# MCU.net
KiCad netlist of a schematic drawn in Altium Designer
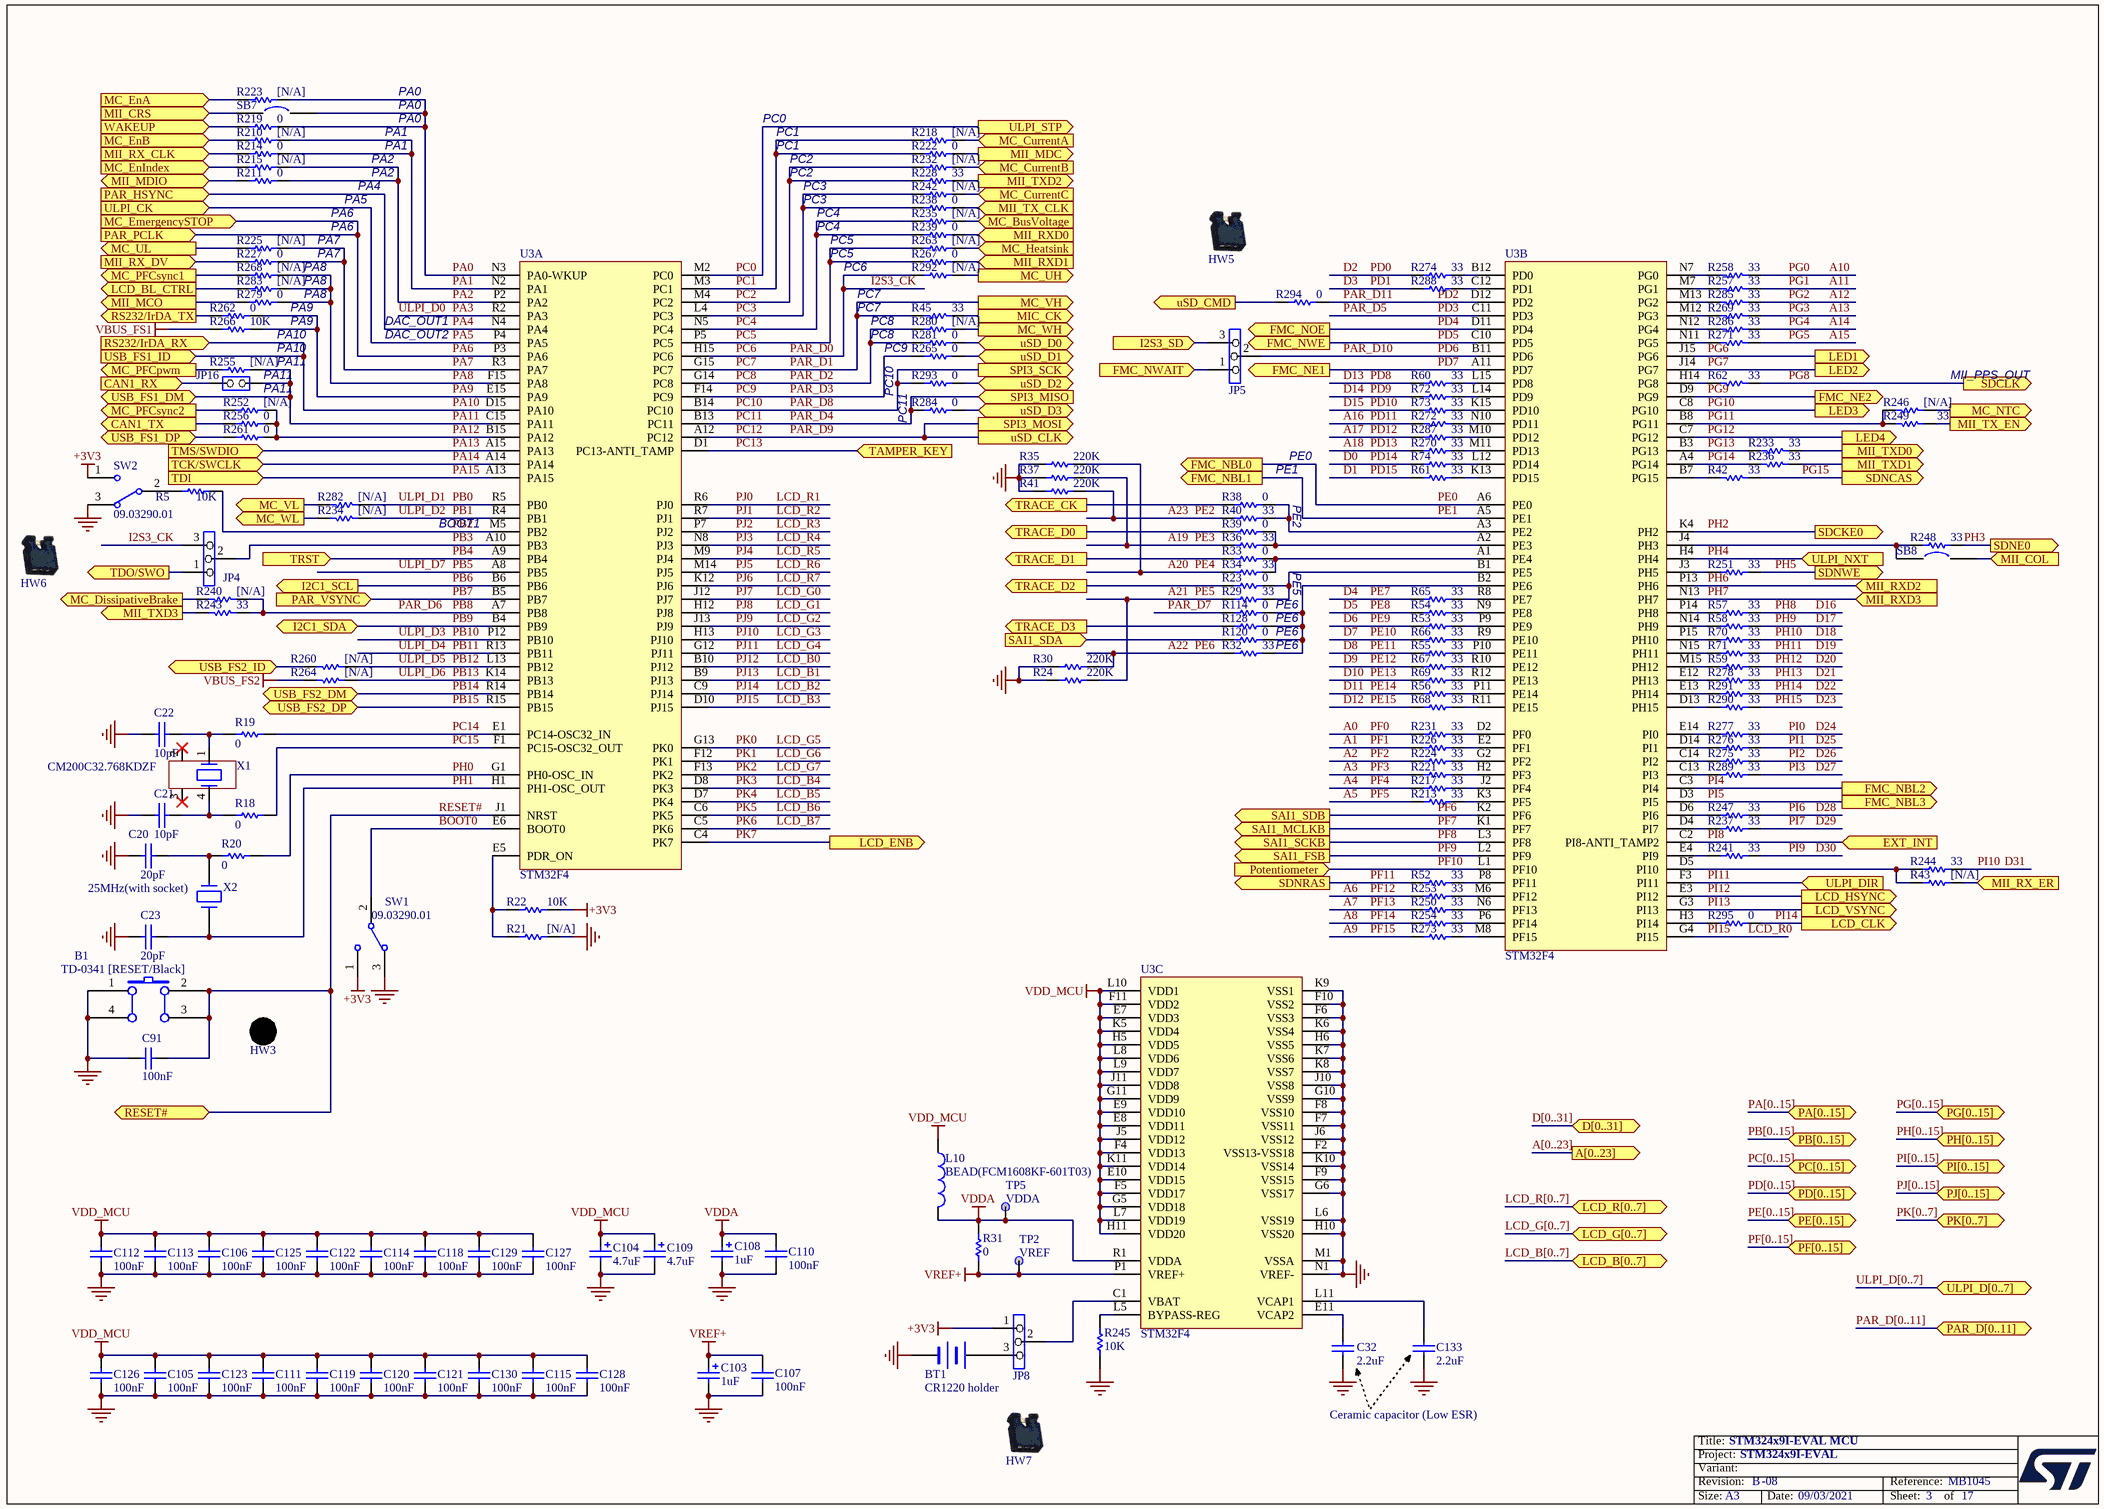
[diagram p0: MCU.SchDoc]

(export (version "E")
  (design (tool "Eeschema 10.0.6"))
  (components
    (comp (ref "B1")
      (value "TD-0341 [RESET/Black]")
      (footprint "PB10")
      (description "SE PUSHBUTTON")
      (libsource (lib "Documents") (part "SW PUSHBUTTON"))
    )
    (comp (ref "BT1")
      (value "CR1220 holder")
      (footprint "BAT_2SM_CR1220")
      (description "Battery")
      (libsource (lib "*") (part "BATTERY"))
    )
    (comp (ref "C20")
      (value "20pF")
      (footprint "0603C")
      (description "Capacitor")
      (libsource (lib "*") (part "CAP"))
    )
    (comp (ref "C21")
      (value "10pF")
      (footprint "0603C")
      (description "Capacitor")
      (libsource (lib "") (part "CAP_1"))
    )
    (comp (ref "C22")
      (value "10pF")
      (footprint "0603C")
      (description "Capacitor")
      (libsource (lib "") (part "CAP_1"))
    )
    (comp (ref "C23")
      (value "20pF")
      (footprint "0603C")
      (description "Capacitor")
      (libsource (lib "*") (part "CAP"))
    )
    (comp (ref "C32")
      (value "2.2uF")
      (footprint "1206C")
      (description "Capacitor")
      (fields (field (name "PUBLISHER") "Altium Limited"))
      (libsource (lib "Miscellaneous Devices") (part "Cap"))
    )
    (comp (ref "C91")
      (value "100nF")
      (footprint "0603C")
      (description "Capacitor")
      (fields (field (name "PUBLISHER") "Altium Limited"))
      (libsource (lib "Miscellaneous Devices") (part "CAP"))
    )
    (comp (ref "C103")
      (value "1uF")
      (footprint "TAN-A")
      (description "Polarized Capacitor (Radial)")
      (fields (field (name "PUBLISHER") "Altium Limited"))
      (libsource (lib "Miscellaneous Devices") (part "Cap Pol1"))
    )
    (comp (ref "C104")
      (value "4.7uF")
      (footprint "TAN-A")
      (description "Polarized Capacitor (Radial)")
      (fields (field (name "PUBLISHER") "Altium Limited"))
      (libsource (lib "Miscellaneous Devices") (part "Cap Pol1"))
    )
    (comp (ref "C105")
      (value "100nF")
      (footprint "0402C")
      (description "Capacitor")
      (fields (field (name "PUBLISHER") "Altium Limited"))
      (libsource (lib "Miscellaneous Devices") (part "CAP"))
    )
    (comp (ref "C106")
      (value "100nF")
      (footprint "0402C")
      (description "Capacitor")
      (fields (field (name "PUBLISHER") "Altium Limited"))
      (libsource (lib "Miscellaneous Devices") (part "CAP"))
    )
    (comp (ref "C107")
      (value "100nF")
      (footprint "0402C")
      (description "Capacitor")
      (fields (field (name "PUBLISHER") "Altium Limited"))
      (libsource (lib "Miscellaneous Devices") (part "Cap"))
    )
    (comp (ref "C108")
      (value "1uF")
      (footprint "TAN-A")
      (description "Polarized Capacitor (Radial)")
      (fields (field (name "PUBLISHER") "Altium Limited"))
      (libsource (lib "Miscellaneous Devices") (part "Cap Pol1"))
    )
    (comp (ref "C109")
      (value "4.7uF")
      (footprint "TAN-A")
      (description "Polarized Capacitor (Radial)")
      (fields (field (name "PUBLISHER") "Altium Limited"))
      (libsource (lib "Miscellaneous Devices") (part "Cap Pol1"))
    )
    (comp (ref "C110")
      (value "100nF")
      (footprint "0402C")
      (description "Capacitor")
      (fields (field (name "PUBLISHER") "Altium Limited"))
      (libsource (lib "Miscellaneous Devices") (part "Cap"))
    )
    (comp (ref "C111")
      (value "100nF")
      (footprint "0402C")
      (description "Capacitor")
      (fields (field (name "PUBLISHER") "Altium Limited"))
      (libsource (lib "Miscellaneous Devices") (part "CAP"))
    )
    (comp (ref "C112")
      (value "100nF")
      (footprint "0402C")
      (description "Capacitor")
      (fields (field (name "PUBLISHER") "Altium Limited"))
      (libsource (lib "Miscellaneous Devices") (part "CAP"))
    )
    (comp (ref "C113")
      (value "100nF")
      (footprint "0402C")
      (description "Capacitor")
      (fields (field (name "PUBLISHER") "Altium Limited"))
      (libsource (lib "Miscellaneous Devices") (part "CAP"))
    )
    (comp (ref "C114")
      (value "100nF")
      (footprint "0402C")
      (description "Capacitor")
      (fields (field (name "PUBLISHER") "Altium Limited"))
      (libsource (lib "Miscellaneous Devices") (part "CAP"))
    )
    (comp (ref "C115")
      (value "100nF")
      (footprint "0402C")
      (description "Capacitor")
      (fields (field (name "PUBLISHER") "Altium Limited"))
      (libsource (lib "Miscellaneous Devices") (part "CAP"))
    )
    (comp (ref "C118")
      (value "100nF")
      (footprint "0402C")
      (description "Capacitor")
      (fields (field (name "PUBLISHER") "Altium Limited"))
      (libsource (lib "Miscellaneous Devices") (part "CAP"))
    )
    (comp (ref "C119")
      (value "100nF")
      (footprint "0402C")
      (description "Capacitor")
      (fields (field (name "PUBLISHER") "Altium Limited"))
      (libsource (lib "Miscellaneous Devices") (part "CAP"))
    )
    (comp (ref "C120")
      (value "100nF")
      (footprint "0402C")
      (description "Capacitor")
      (fields (field (name "PUBLISHER") "Altium Limited"))
      (libsource (lib "Miscellaneous Devices") (part "CAP"))
    )
    (comp (ref "C121")
      (value "100nF")
      (footprint "0402C")
      (description "Capacitor")
      (fields (field (name "PUBLISHER") "Altium Limited"))
      (libsource (lib "Miscellaneous Devices") (part "CAP"))
    )
    (comp (ref "C122")
      (value "100nF")
      (footprint "0402C")
      (description "Capacitor")
      (fields (field (name "PUBLISHER") "Altium Limited"))
      (libsource (lib "Miscellaneous Devices") (part "CAP"))
    )
    (comp (ref "C123")
      (value "100nF")
      (footprint "0402C")
      (description "Capacitor")
      (fields (field (name "PUBLISHER") "Altium Limited"))
      (libsource (lib "Miscellaneous Devices") (part "CAP"))
    )
    (comp (ref "C125")
      (value "100nF")
      (footprint "0402C")
      (description "Capacitor")
      (fields (field (name "PUBLISHER") "Altium Limited"))
      (libsource (lib "Miscellaneous Devices") (part "CAP"))
    )
    (comp (ref "C126")
      (value "100nF")
      (footprint "0402C")
      (description "Capacitor")
      (fields (field (name "PUBLISHER") "Altium Limited"))
      (libsource (lib "Miscellaneous Devices") (part "CAP"))
    )
    (comp (ref "C127")
      (value "100nF")
      (footprint "0402C")
      (description "Capacitor")
      (fields (field (name "PUBLISHER") "Altium Limited"))
      (libsource (lib "Miscellaneous Devices") (part "CAP"))
    )
    (comp (ref "C128")
      (value "100nF")
      (footprint "0402C")
      (description "Capacitor")
      (fields (field (name "PUBLISHER") "Altium Limited"))
      (libsource (lib "Miscellaneous Devices") (part "CAP"))
    )
    (comp (ref "C129")
      (value "100nF")
      (footprint "0402C")
      (description "Capacitor")
      (fields (field (name "PUBLISHER") "Altium Limited"))
      (libsource (lib "Miscellaneous Devices") (part "CAP"))
    )
    (comp (ref "C130")
      (value "100nF")
      (footprint "0402C")
      (description "Capacitor")
      (fields (field (name "PUBLISHER") "Altium Limited"))
      (libsource (lib "Miscellaneous Devices") (part "CAP"))
    )
    (comp (ref "C133")
      (value "2.2uF")
      (footprint "1206C")
      (description "Capacitor")
      (fields (field (name "PUBLISHER") "Altium Limited"))
      (libsource (lib "Miscellaneous Devices") (part "Cap"))
    )
    (comp (ref "HW3") (value "BUTTON_HAT_BLACK") (libsource (lib "mb1045") (part "BUTTON_HAT_BLACK")))
    (comp (ref "HW5") (value "JUMPER_OPEN") (libsource (lib "mb1045") (part "JUMPER_OPEN")))
    (comp (ref "HW6") (value "JUMPER_OPEN") (libsource (lib "mb1045") (part "JUMPER_OPEN")))
    (comp (ref "HW7") (value "JUMPER_OPEN") (libsource (lib "mb1045") (part "JUMPER_OPEN")))
    (comp (ref "JP4") (value "~") (footprint "SIP3") (libsource (lib "STR910_SCHLIB") (part "Jumper3")))
    (comp (ref "JP5") (value "~") (footprint "SIP3") (libsource (lib "STR910_SCHLIB") (part "Jumper3")))
    (comp (ref "JP8") (value "~") (footprint "SIP3") (libsource (lib "") (part "Jumper3_1")))
    (comp (ref "JP16") (value "~") (footprint "SIP2") (libsource (lib "*") (part "JP2")))
    (comp (ref "L10")
      (value "BEAD(FCM1608KF-601T03)")
      (footprint "0603L")
      (description "Inductor")
      (fields (field (name "PUBLISHER") "Altium Limited"))
      (libsource (lib "Miscellaneous Devices") (part "Inductor"))
    )
    (comp (ref "R5")
      (value "10K")
      (footprint "0603R")
      (description "Resistor")
      (fields (field (name "PUBLISHER") "Altium Limited"))
      (libsource (lib "Miscellaneous Devices") (part "Res1"))
    )
    (comp (ref "R18")
      (value "0")
      (footprint "0603R")
      (description "Resistor")
      (fields (field (name "PUBLISHER") "Altium Limited"))
      (libsource (lib "") (part "Res1_1"))
    )
    (comp (ref "R19")
      (value "0")
      (footprint "0603R")
      (description "Resistor")
      (fields (field (name "PUBLISHER") "Altium Limited"))
      (libsource (lib "") (part "Res1_1"))
    )
    (comp (ref "R20")
      (value "0")
      (footprint "0603R")
      (description "Resistor")
      (fields (field (name "PUBLISHER") "Altium Limited"))
      (libsource (lib "Miscellaneous Devices") (part "Res1"))
    )
    (comp (ref "R21")
      (value "[N/A]")
      (footprint "0603R")
      (description "Resistor")
      (fields (field (name "PUBLISHER") "Altium Limited"))
      (libsource (lib "Miscellaneous Devices") (part "Res1"))
    )
    (comp (ref "R22")
      (value "10K")
      (footprint "0603R")
      (description "Resistor")
      (fields (field (name "PUBLISHER") "Altium Limited"))
      (libsource (lib "Miscellaneous Devices") (part "Res1"))
    )
    (comp (ref "R23")
      (value "0")
      (footprint "0603R")
      (description "Resistor")
      (fields (field (name "PUBLISHER") "Altium Limited"))
      (libsource (lib "Miscellaneous Devices") (part "Res1"))
    )
    (comp (ref "R24")
      (value "220K")
      (footprint "0603R")
      (description "Resistor")
      (fields (field (name "PUBLISHER") "Altium Limited"))
      (libsource (lib "Miscellaneous Devices") (part "res1"))
    )
    (comp (ref "R29")
      (value "33")
      (footprint "0402R")
      (description "Resistor")
      (fields (field (name "PUBLISHER") "Altium Limited"))
      (libsource (lib "Miscellaneous Devices") (part "Res1"))
    )
    (comp (ref "R30")
      (value "220K")
      (footprint "0603R")
      (description "Resistor")
      (fields (field (name "PUBLISHER") "Altium Limited"))
      (libsource (lib "Miscellaneous Devices") (part "res1"))
    )
    (comp (ref "R31")
      (value "0")
      (footprint "0603R")
      (description "Resistor")
      (fields (field (name "PUBLISHER") "Altium Limited"))
      (libsource (lib "Miscellaneous Devices") (part "Res1"))
    )
    (comp (ref "R32")
      (value "33")
      (footprint "0402R")
      (description "Resistor")
      (fields (field (name "PUBLISHER") "Altium Limited"))
      (libsource (lib "Miscellaneous Devices") (part "Res1"))
    )
    (comp (ref "R33")
      (value "0")
      (footprint "0603R")
      (description "Resistor")
      (fields (field (name "PUBLISHER") "Altium Limited"))
      (libsource (lib "Miscellaneous Devices") (part "Res1"))
    )
    (comp (ref "R34")
      (value "33")
      (footprint "0402R")
      (description "Resistor")
      (fields (field (name "PUBLISHER") "Altium Limited"))
      (libsource (lib "Miscellaneous Devices") (part "Res1"))
    )
    (comp (ref "R35")
      (value "220K")
      (footprint "0603R")
      (description "Resistor")
      (fields (field (name "PUBLISHER") "Altium Limited"))
      (libsource (lib "Miscellaneous Devices") (part "res1"))
    )
    (comp (ref "R36")
      (value "33")
      (footprint "0402R")
      (description "Resistor")
      (fields (field (name "PUBLISHER") "Altium Limited"))
      (libsource (lib "Miscellaneous Devices") (part "Res1"))
    )
    (comp (ref "R37")
      (value "220K")
      (footprint "0603R")
      (description "Resistor")
      (fields (field (name "PUBLISHER") "Altium Limited"))
      (libsource (lib "Miscellaneous Devices") (part "res1"))
    )
    (comp (ref "R38")
      (value "0")
      (footprint "0603R")
      (description "Resistor")
      (fields (field (name "PUBLISHER") "Altium Limited"))
      (libsource (lib "Miscellaneous Devices") (part "Res1"))
    )
    (comp (ref "R39")
      (value "0")
      (footprint "0603R")
      (description "Resistor")
      (fields (field (name "PUBLISHER") "Altium Limited"))
      (libsource (lib "Miscellaneous Devices") (part "Res1"))
    )
    (comp (ref "R40")
      (value "33")
      (footprint "0402R")
      (description "Resistor")
      (fields (field (name "PUBLISHER") "Altium Limited"))
      (libsource (lib "Miscellaneous Devices") (part "Res1"))
    )
    (comp (ref "R41")
      (value "220K")
      (footprint "0603R")
      (description "Resistor")
      (fields (field (name "PUBLISHER") "Altium Limited"))
      (libsource (lib "Miscellaneous Devices") (part "res1"))
    )
    (comp (ref "R42")
      (value "33")
      (footprint "0402R")
      (description "Resistor")
      (fields (field (name "PUBLISHER") "Altium Limited"))
      (libsource (lib "Miscellaneous Devices") (part "Res1"))
    )
    (comp (ref "R43")
      (value "[N/A]")
      (footprint "0603R")
      (description "Resistor")
      (fields (field (name "PUBLISHER") "Altium Limited"))
      (libsource (lib "Miscellaneous Devices") (part "Res1"))
    )
    (comp (ref "R45")
      (value "33")
      (footprint "0603R")
      (description "Resistor")
      (fields (field (name "PUBLISHER") "Altium Limited"))
      (libsource (lib "Miscellaneous Devices") (part "Res1"))
    )
    (comp (ref "R52")
      (value "33")
      (footprint "0402R")
      (description "Resistor")
      (fields (field (name "PUBLISHER") "Altium Limited"))
      (libsource (lib "Miscellaneous Devices") (part "Res1"))
    )
    (comp (ref "R53")
      (value "33")
      (footprint "0402R")
      (description "Resistor")
      (fields (field (name "PUBLISHER") "Altium Limited"))
      (libsource (lib "Miscellaneous Devices") (part "Res1"))
    )
    (comp (ref "R54")
      (value "33")
      (footprint "0402R")
      (description "Resistor")
      (fields (field (name "PUBLISHER") "Altium Limited"))
      (libsource (lib "Miscellaneous Devices") (part "Res1"))
    )
    (comp (ref "R55")
      (value "33")
      (footprint "0402R")
      (description "Resistor")
      (fields (field (name "PUBLISHER") "Altium Limited"))
      (libsource (lib "Miscellaneous Devices") (part "Res1"))
    )
    (comp (ref "R56")
      (value "33")
      (footprint "0402R")
      (description "Resistor")
      (fields (field (name "PUBLISHER") "Altium Limited"))
      (libsource (lib "Miscellaneous Devices") (part "Res1"))
    )
    (comp (ref "R57")
      (value "33")
      (footprint "0402R")
      (description "Resistor")
      (fields (field (name "PUBLISHER") "Altium Limited"))
      (libsource (lib "Miscellaneous Devices") (part "Res1"))
    )
    (comp (ref "R58")
      (value "33")
      (footprint "0402R")
      (description "Resistor")
      (fields (field (name "PUBLISHER") "Altium Limited"))
      (libsource (lib "Miscellaneous Devices") (part "Res1"))
    )
    (comp (ref "R59")
      (value "33")
      (footprint "0402R")
      (description "Resistor")
      (fields (field (name "PUBLISHER") "Altium Limited"))
      (libsource (lib "Miscellaneous Devices") (part "Res1"))
    )
    (comp (ref "R60")
      (value "33")
      (footprint "0402R")
      (description "Resistor")
      (fields (field (name "PUBLISHER") "Altium Limited"))
      (libsource (lib "Miscellaneous Devices") (part "Res1"))
    )
    (comp (ref "R61")
      (value "33")
      (footprint "0402R")
      (description "Resistor")
      (fields (field (name "PUBLISHER") "Altium Limited"))
      (libsource (lib "Miscellaneous Devices") (part "Res1"))
    )
    (comp (ref "R62")
      (value "33")
      (footprint "0402R")
      (description "Resistor")
      (fields (field (name "PUBLISHER") "Altium Limited"))
      (libsource (lib "Miscellaneous Devices") (part "Res1"))
    )
    (comp (ref "R65")
      (value "33")
      (footprint "0402R")
      (description "Resistor")
      (fields (field (name "PUBLISHER") "Altium Limited"))
      (libsource (lib "Miscellaneous Devices") (part "Res1"))
    )
    (comp (ref "R66")
      (value "33")
      (footprint "0402R")
      (description "Resistor")
      (fields (field (name "PUBLISHER") "Altium Limited"))
      (libsource (lib "Miscellaneous Devices") (part "Res1"))
    )
    (comp (ref "R67")
      (value "33")
      (footprint "0402R")
      (description "Resistor")
      (fields (field (name "PUBLISHER") "Altium Limited"))
      (libsource (lib "Miscellaneous Devices") (part "Res1"))
    )
    (comp (ref "R68")
      (value "33")
      (footprint "0402R")
      (description "Resistor")
      (fields (field (name "PUBLISHER") "Altium Limited"))
      (libsource (lib "Miscellaneous Devices") (part "Res1"))
    )
    (comp (ref "R69")
      (value "33")
      (footprint "0402R")
      (description "Resistor")
      (fields (field (name "PUBLISHER") "Altium Limited"))
      (libsource (lib "Miscellaneous Devices") (part "Res1"))
    )
    (comp (ref "R70")
      (value "33")
      (footprint "0402R")
      (description "Resistor")
      (fields (field (name "PUBLISHER") "Altium Limited"))
      (libsource (lib "Miscellaneous Devices") (part "Res1"))
    )
    (comp (ref "R71")
      (value "33")
      (footprint "0402R")
      (description "Resistor")
      (fields (field (name "PUBLISHER") "Altium Limited"))
      (libsource (lib "Miscellaneous Devices") (part "Res1"))
    )
    (comp (ref "R72")
      (value "33")
      (footprint "0402R")
      (description "Resistor")
      (fields (field (name "PUBLISHER") "Altium Limited"))
      (libsource (lib "Miscellaneous Devices") (part "Res1"))
    )
    (comp (ref "R73")
      (value "33")
      (footprint "0402R")
      (description "Resistor")
      (fields (field (name "PUBLISHER") "Altium Limited"))
      (libsource (lib "Miscellaneous Devices") (part "Res1"))
    )
    (comp (ref "R74")
      (value "33")
      (footprint "0402R")
      (description "Resistor")
      (fields (field (name "PUBLISHER") "Altium Limited"))
      (libsource (lib "Miscellaneous Devices") (part "Res1"))
    )
    (comp (ref "R114")
      (value "0")
      (footprint "0603R")
      (description "Resistor")
      (fields (field (name "PUBLISHER") "Altium Limited"))
      (libsource (lib "Miscellaneous Devices") (part "Res1"))
    )
    (comp (ref "R120")
      (value "0")
      (footprint "0603R")
      (description "Resistor")
      (fields (field (name "PUBLISHER") "Altium Limited"))
      (libsource (lib "Miscellaneous Devices") (part "Res1"))
    )
    (comp (ref "R128")
      (value "0")
      (footprint "0603R")
      (description "Resistor")
      (fields (field (name "PUBLISHER") "Altium Limited"))
      (libsource (lib "Miscellaneous Devices") (part "Res1"))
    )
    (comp (ref "R210")
      (value "[N/A]")
      (footprint "0603R")
      (description "Resistor")
      (fields (field (name "PUBLISHER") "Altium Limited"))
      (libsource (lib "Miscellaneous Devices") (part "Res1"))
    )
    (comp (ref "R211")
      (value "0")
      (footprint "0603R")
      (description "Resistor")
      (fields (field (name "PUBLISHER") "Altium Limited"))
      (libsource (lib "Miscellaneous Devices") (part "Res1"))
    )
    (comp (ref "R213")
      (value "33")
      (footprint "0402R")
      (description "Resistor")
      (fields (field (name "PUBLISHER") "Altium Limited"))
      (libsource (lib "Miscellaneous Devices") (part "Res1"))
    )
    (comp (ref "R214")
      (value "0")
      (footprint "0603R")
      (description "Resistor")
      (fields (field (name "PUBLISHER") "Altium Limited"))
      (libsource (lib "Miscellaneous Devices") (part "Res1"))
    )
    (comp (ref "R215")
      (value "[N/A]")
      (footprint "0603R")
      (description "Resistor")
      (fields (field (name "PUBLISHER") "Altium Limited"))
      (libsource (lib "Miscellaneous Devices") (part "Res1"))
    )
    (comp (ref "R217")
      (value "33")
      (footprint "0402R")
      (description "Resistor")
      (fields (field (name "PUBLISHER") "Altium Limited"))
      (libsource (lib "Miscellaneous Devices") (part "Res1"))
    )
    (comp (ref "R218")
      (value "[N/A]")
      (footprint "0603R")
      (description "Resistor")
      (fields (field (name "PUBLISHER") "Altium Limited"))
      (libsource (lib "Miscellaneous Devices") (part "Res1"))
    )
    (comp (ref "R219")
      (value "0")
      (footprint "0603R")
      (description "Resistor")
      (fields (field (name "PUBLISHER") "Altium Limited"))
      (libsource (lib "Miscellaneous Devices") (part "Res1"))
    )
    (comp (ref "R221")
      (value "33")
      (footprint "0402R")
      (description "Resistor")
      (fields (field (name "PUBLISHER") "Altium Limited"))
      (libsource (lib "Miscellaneous Devices") (part "Res1"))
    )
    (comp (ref "R222")
      (value "0")
      (footprint "0603R")
      (description "Resistor")
      (fields (field (name "PUBLISHER") "Altium Limited"))
      (libsource (lib "Miscellaneous Devices") (part "Res1"))
    )
    (comp (ref "R223")
      (value "[N/A]")
      (footprint "0603R")
      (description "Resistor")
      (fields (field (name "PUBLISHER") "Altium Limited"))
      (libsource (lib "Miscellaneous Devices") (part "Res1"))
    )
    (comp (ref "R224")
      (value "33")
      (footprint "0402R")
      (description "Resistor")
      (fields (field (name "PUBLISHER") "Altium Limited"))
      (libsource (lib "Miscellaneous Devices") (part "Res1"))
    )
    (comp (ref "R225")
      (value "[N/A]")
      (footprint "0603R")
      (description "Resistor")
      (fields (field (name "PUBLISHER") "Altium Limited"))
      (libsource (lib "Miscellaneous Devices") (part "Res1"))
    )
    (comp (ref "R226")
      (value "33")
      (footprint "0402R")
      (description "Resistor")
      (fields (field (name "PUBLISHER") "Altium Limited"))
      (libsource (lib "Miscellaneous Devices") (part "Res1"))
    )
    (comp (ref "R227")
      (value "0")
      (footprint "0603R")
      (description "Resistor")
      (fields (field (name "PUBLISHER") "Altium Limited"))
      (libsource (lib "Miscellaneous Devices") (part "Res1"))
    )
    (comp (ref "R228")
      (value "33")
      (footprint "0603R")
      (description "Resistor")
      (fields (field (name "PUBLISHER") "Altium Limited"))
      (libsource (lib "Miscellaneous Devices") (part "Res1"))
    )
    (comp (ref "R231")
      (value "33")
      (footprint "0402R")
      (description "Resistor")
      (fields (field (name "PUBLISHER") "Altium Limited"))
      (libsource (lib "Miscellaneous Devices") (part "Res1"))
    )
    (comp (ref "R232")
      (value "[N/A]")
      (footprint "0603R")
      (description "Resistor")
      (fields (field (name "PUBLISHER") "Altium Limited"))
      (libsource (lib "Miscellaneous Devices") (part "Res1"))
    )
    (comp (ref "R233")
      (value "33")
      (footprint "0603R")
      (description "Resistor")
      (fields (field (name "PUBLISHER") "Altium Limited"))
      (libsource (lib "Miscellaneous Devices") (part "Res1"))
    )
    (comp (ref "R234")
      (value "[N/A]")
      (footprint "0603R")
      (description "Resistor")
      (fields (field (name "PUBLISHER") "Altium Limited"))
      (libsource (lib "Miscellaneous Devices") (part "Res1"))
    )
    (comp (ref "R235")
      (value "[N/A]")
      (footprint "0603R")
      (description "Resistor")
      (fields (field (name "PUBLISHER") "Altium Limited"))
      (libsource (lib "Miscellaneous Devices") (part "Res1"))
    )
    (comp (ref "R236")
      (value "33")
      (footprint "0603R")
      (description "Resistor")
      (fields (field (name "PUBLISHER") "Altium Limited"))
      (libsource (lib "Miscellaneous Devices") (part "Res1"))
    )
    (comp (ref "R237")
      (value "33")
      (footprint "0402R")
      (description "Resistor")
      (fields (field (name "PUBLISHER") "Altium Limited"))
      (libsource (lib "Miscellaneous Devices") (part "Res1"))
    )
    (comp (ref "R238")
      (value "0")
      (footprint "0603R")
      (description "Resistor")
      (fields (field (name "PUBLISHER") "Altium Limited"))
      (libsource (lib "Miscellaneous Devices") (part "Res1"))
    )
    (comp (ref "R239")
      (value "0")
      (footprint "0603R")
      (description "Resistor")
      (fields (field (name "PUBLISHER") "Altium Limited"))
      (libsource (lib "Miscellaneous Devices") (part "Res1"))
    )
    (comp (ref "R240")
      (value "[N/A]")
      (footprint "0603R")
      (description "Resistor")
      (fields (field (name "PUBLISHER") "Altium Limited"))
      (libsource (lib "Miscellaneous Devices") (part "Res1"))
    )
    (comp (ref "R241")
      (value "33")
      (footprint "0402R")
      (description "Resistor")
      (fields (field (name "PUBLISHER") "Altium Limited"))
      (libsource (lib "Miscellaneous Devices") (part "Res1"))
    )
    (comp (ref "R242")
      (value "[N/A]")
      (footprint "0603R")
      (description "Resistor")
      (fields (field (name "PUBLISHER") "Altium Limited"))
      (libsource (lib "Miscellaneous Devices") (part "Res1"))
    )
    (comp (ref "R243")
      (value "33")
      (footprint "0603R")
      (description "Resistor")
      (fields (field (name "PUBLISHER") "Altium Limited"))
      (libsource (lib "Miscellaneous Devices") (part "Res1"))
    )
    (comp (ref "R244")
      (value "33")
      (footprint "0402R")
      (description "Resistor")
      (fields (field (name "PUBLISHER") "Altium Limited"))
      (libsource (lib "Miscellaneous Devices") (part "Res1"))
    )
    (comp (ref "R245")
      (value "10K")
      (footprint "0603R")
      (description "Resistor")
      (fields (field (name "PUBLISHER") "Altium Limited"))
      (libsource (lib "Miscellaneous Devices") (part "Res1"))
    )
    (comp (ref "R246")
      (value "[N/A]")
      (footprint "0603R")
      (description "Resistor")
      (fields (field (name "PUBLISHER") "Altium Limited"))
      (libsource (lib "Miscellaneous Devices") (part "Res1"))
    )
    (comp (ref "R247")
      (value "33")
      (footprint "0402R")
      (description "Resistor")
      (fields (field (name "PUBLISHER") "Altium Limited"))
      (libsource (lib "Miscellaneous Devices") (part "Res1"))
    )
    (comp (ref "R248")
      (value "33")
      (footprint "0402R")
      (description "Resistor")
      (fields (field (name "PUBLISHER") "Altium Limited"))
      (libsource (lib "Miscellaneous Devices") (part "Res1"))
    )
    (comp (ref "R249")
      (value "33")
      (footprint "0603R")
      (description "Resistor")
      (fields (field (name "PUBLISHER") "Altium Limited"))
      (libsource (lib "Miscellaneous Devices") (part "Res1"))
    )
    (comp (ref "R250")
      (value "33")
      (footprint "0402R")
      (description "Resistor")
      (fields (field (name "PUBLISHER") "Altium Limited"))
      (libsource (lib "Miscellaneous Devices") (part "Res1"))
    )
    (comp (ref "R251")
      (value "33")
      (footprint "0402R")
      (description "Resistor")
      (fields (field (name "PUBLISHER") "Altium Limited"))
      (libsource (lib "Miscellaneous Devices") (part "Res1"))
    )
    (comp (ref "R252")
      (value "[N/A]")
      (footprint "0603R")
      (description "Resistor")
      (fields (field (name "PUBLISHER") "Altium Limited"))
      (libsource (lib "Miscellaneous Devices") (part "Res1"))
    )
    (comp (ref "R253")
      (value "33")
      (footprint "0402R")
      (description "Resistor")
      (fields (field (name "PUBLISHER") "Altium Limited"))
      (libsource (lib "Miscellaneous Devices") (part "Res1"))
    )
    (comp (ref "R254")
      (value "33")
      (footprint "0402R")
      (description "Resistor")
      (fields (field (name "PUBLISHER") "Altium Limited"))
      (libsource (lib "Miscellaneous Devices") (part "Res1"))
    )
    (comp (ref "R255")
      (value "[N/A]")
      (footprint "0603R")
      (description "Resistor")
      (fields (field (name "PUBLISHER") "Altium Limited"))
      (libsource (lib "Miscellaneous Devices") (part "Res1"))
    )
    (comp (ref "R256")
      (value "0")
      (footprint "0603R")
      (description "Resistor")
      (fields (field (name "PUBLISHER") "Altium Limited"))
      (libsource (lib "Miscellaneous Devices") (part "Res1"))
    )
    (comp (ref "R257")
      (value "33")
      (footprint "0402R")
      (description "Resistor")
      (fields (field (name "PUBLISHER") "Altium Limited"))
      (libsource (lib "Miscellaneous Devices") (part "Res1"))
    )
    (comp (ref "R258")
      (value "33")
      (footprint "0402R")
      (description "Resistor")
      (fields (field (name "PUBLISHER") "Altium Limited"))
      (libsource (lib "Miscellaneous Devices") (part "Res1"))
    )
    (comp (ref "R260")
      (value "[N/A]")
      (footprint "0603R")
      (description "Resistor")
      (fields (field (name "PUBLISHER") "Altium Limited"))
      (libsource (lib "Miscellaneous Devices") (part "Res1"))
    )
    (comp (ref "R261")
      (value "0")
      (footprint "0603R")
      (description "Resistor")
      (fields (field (name "PUBLISHER") "Altium Limited"))
      (libsource (lib "Miscellaneous Devices") (part "Res1"))
    )
    (comp (ref "R262")
      (value "0")
      (footprint "0603R")
      (description "Resistor")
      (fields (field (name "PUBLISHER") "Altium Limited"))
      (libsource (lib "Miscellaneous Devices") (part "Res1"))
    )
    (comp (ref "R263")
      (value "[N/A]")
      (footprint "0603R")
      (description "Resistor")
      (fields (field (name "PUBLISHER") "Altium Limited"))
      (libsource (lib "Miscellaneous Devices") (part "Res1"))
    )
    (comp (ref "R264")
      (value "[N/A]")
      (footprint "0603R")
      (description "Resistor")
      (fields (field (name "PUBLISHER") "Altium Limited"))
      (libsource (lib "Miscellaneous Devices") (part "Res1"))
    )
    (comp (ref "R265")
      (value "0")
      (footprint "0603R")
      (description "Resistor")
      (fields (field (name "PUBLISHER") "Altium Limited"))
      (libsource (lib "Miscellaneous Devices") (part "Res1"))
    )
    (comp (ref "R266")
      (value "10K")
      (footprint "0603R")
      (description "Resistor")
      (fields (field (name "PUBLISHER") "Altium Limited"))
      (libsource (lib "Miscellaneous Devices") (part "res1"))
    )
    (comp (ref "R267")
      (value "0")
      (footprint "0603R")
      (description "Resistor")
      (fields (field (name "PUBLISHER") "Altium Limited"))
      (libsource (lib "Miscellaneous Devices") (part "Res1"))
    )
    (comp (ref "R268")
      (value "[N/A]")
      (footprint "0603R")
      (description "Resistor")
      (fields (field (name "PUBLISHER") "Altium Limited"))
      (libsource (lib "Miscellaneous Devices") (part "Res1"))
    )
    (comp (ref "R269")
      (value "33")
      (footprint "0402R")
      (description "Resistor")
      (fields (field (name "PUBLISHER") "Altium Limited"))
      (libsource (lib "Miscellaneous Devices") (part "Res1"))
    )
    (comp (ref "R270")
      (value "33")
      (footprint "0402R")
      (description "Resistor")
      (fields (field (name "PUBLISHER") "Altium Limited"))
      (libsource (lib "Miscellaneous Devices") (part "Res1"))
    )
    (comp (ref "R271")
      (value "33")
      (footprint "0402R")
      (description "Resistor")
      (fields (field (name "PUBLISHER") "Altium Limited"))
      (libsource (lib "Miscellaneous Devices") (part "Res1"))
    )
    (comp (ref "R272")
      (value "33")
      (footprint "0402R")
      (description "Resistor")
      (fields (field (name "PUBLISHER") "Altium Limited"))
      (libsource (lib "Miscellaneous Devices") (part "Res1"))
    )
    (comp (ref "R273")
      (value "33")
      (footprint "0402R")
      (description "Resistor")
      (fields (field (name "PUBLISHER") "Altium Limited"))
      (libsource (lib "Miscellaneous Devices") (part "Res1"))
    )
    (comp (ref "R274")
      (value "33")
      (footprint "0402R")
      (description "Resistor")
      (fields (field (name "PUBLISHER") "Altium Limited"))
      (libsource (lib "Miscellaneous Devices") (part "Res1"))
    )
    (comp (ref "R275")
      (value "33")
      (footprint "0402R")
      (description "Resistor")
      (fields (field (name "PUBLISHER") "Altium Limited"))
      (libsource (lib "Miscellaneous Devices") (part "Res1"))
    )
    (comp (ref "R276")
      (value "33")
      (footprint "0402R")
      (description "Resistor")
      (fields (field (name "PUBLISHER") "Altium Limited"))
      (libsource (lib "Miscellaneous Devices") (part "Res1"))
    )
    (comp (ref "R277")
      (value "33")
      (footprint "0402R")
      (description "Resistor")
      (fields (field (name "PUBLISHER") "Altium Limited"))
      (libsource (lib "Miscellaneous Devices") (part "Res1"))
    )
    (comp (ref "R278")
      (value "33")
      (footprint "0402R")
      (description "Resistor")
      (fields (field (name "PUBLISHER") "Altium Limited"))
      (libsource (lib "Miscellaneous Devices") (part "Res1"))
    )
    (comp (ref "R279")
      (value "0")
      (footprint "0603R")
      (description "Resistor")
      (fields (field (name "PUBLISHER") "Altium Limited"))
      (libsource (lib "Miscellaneous Devices") (part "Res1"))
    )
    (comp (ref "R280")
      (value "[N/A]")
      (footprint "0603R")
      (description "Resistor")
      (fields (field (name "PUBLISHER") "Altium Limited"))
      (libsource (lib "Miscellaneous Devices") (part "Res1"))
    )
    (comp (ref "R281")
      (value "0")
      (footprint "0603R")
      (description "Resistor")
      (fields (field (name "PUBLISHER") "Altium Limited"))
      (libsource (lib "Miscellaneous Devices") (part "Res1"))
    )
    (comp (ref "R282")
      (value "[N/A]")
      (footprint "0603R")
      (description "Resistor")
      (fields (field (name "PUBLISHER") "Altium Limited"))
      (libsource (lib "Miscellaneous Devices") (part "Res1"))
    )
    (comp (ref "R283")
      (value "[N/A]")
      (footprint "0603R")
      (description "Resistor")
      (fields (field (name "PUBLISHER") "Altium Limited"))
      (libsource (lib "Miscellaneous Devices") (part "Res1"))
    )
    (comp (ref "R284")
      (value "0")
      (footprint "0603R")
      (description "Resistor")
      (fields (field (name "PUBLISHER") "Altium Limited"))
      (libsource (lib "Miscellaneous Devices") (part "Res1"))
    )
    (comp (ref "R285")
      (value "33")
      (footprint "0402R")
      (description "Resistor")
      (fields (field (name "PUBLISHER") "Altium Limited"))
      (libsource (lib "Miscellaneous Devices") (part "Res1"))
    )
    (comp (ref "R286")
      (value "33")
      (footprint "0402R")
      (description "Resistor")
      (fields (field (name "PUBLISHER") "Altium Limited"))
      (libsource (lib "Miscellaneous Devices") (part "Res1"))
    )
    (comp (ref "R287")
      (value "33")
      (footprint "0402R")
      (description "Resistor")
      (fields (field (name "PUBLISHER") "Altium Limited"))
      (libsource (lib "Miscellaneous Devices") (part "Res1"))
    )
    (comp (ref "R288")
      (value "33")
      (footprint "0402R")
      (description "Resistor")
      (fields (field (name "PUBLISHER") "Altium Limited"))
      (libsource (lib "Miscellaneous Devices") (part "Res1"))
    )
    (comp (ref "R289")
      (value "33")
      (footprint "0402R")
      (description "Resistor")
      (fields (field (name "PUBLISHER") "Altium Limited"))
      (libsource (lib "Miscellaneous Devices") (part "Res1"))
    )
    (comp (ref "R290")
      (value "33")
      (footprint "0402R")
      (description "Resistor")
      (fields (field (name "PUBLISHER") "Altium Limited"))
      (libsource (lib "Miscellaneous Devices") (part "Res1"))
    )
    (comp (ref "R291")
      (value "33")
      (footprint "0402R")
      (description "Resistor")
      (fields (field (name "PUBLISHER") "Altium Limited"))
      (libsource (lib "Miscellaneous Devices") (part "Res1"))
    )
    (comp (ref "R292")
      (value "[N/A]")
      (footprint "0603R")
      (description "Resistor")
      (fields (field (name "PUBLISHER") "Altium Limited"))
      (libsource (lib "Miscellaneous Devices") (part "Res1"))
    )
    (comp (ref "R293")
      (value "0")
      (footprint "0603R")
      (description "Resistor")
      (fields (field (name "PUBLISHER") "Altium Limited"))
      (libsource (lib "Miscellaneous Devices") (part "Res1"))
    )
    (comp (ref "R294")
      (value "0")
      (footprint "0603R")
      (description "Resistor")
      (fields (field (name "PUBLISHER") "Altium Limited"))
      (libsource (lib "Miscellaneous Devices") (part "Res1"))
    )
    (comp (ref "R295")
      (value "0")
      (footprint "0603R")
      (description "Resistor")
      (fields (field (name "PUBLISHER") "Altium Limited"))
      (libsource (lib "Miscellaneous Devices") (part "Res1"))
    )
    (comp (ref "SB7")
      (value "~")
      (footprint "JP2_SMD")
      (description "Circuit Breaker")
      (fields (field (name "PUBLISHER") "Altium Limited"))
      (libsource (lib "Miscellaneous Devices") (part "Circuit Breaker"))
    )
    (comp (ref "SB8")
      (value "~")
      (footprint "JP2_SMD")
      (description "Circuit Breaker")
      (fields (field (name "PUBLISHER") "Altium Limited"))
      (libsource (lib "Miscellaneous Devices") (part "Circuit Breaker"))
    )
    (comp (ref "SW1")
      (value "09.03290.01")
      (footprint "SW1_3TH_2R54_10X2R5")
      (description "SPDT Subminiature Toggle Switch, Right Angle Mounting, Vertical Actuation")
      (fields (field (name "PUBLISHER") "Altium Limited"))
      (libsource (lib "mb1045") (part "SW-SPDT"))
    )
    (comp (ref "SW2")
      (value "09.03290.01")
      (footprint "SW1_3TH_2R54_10X2R5")
      (description "SPDT Subminiature Toggle Switch, Right Angle Mounting, Vertical Actuation")
      (fields (field (name "PUBLISHER") "Altium Limited"))
      (libsource (lib "mb1045") (part "SW-SPDT"))
    )
    (comp (ref "TP2") (value "VREF") (footprint "TP") (libsource (lib "*") (part "TP")))
    (comp (ref "TP5") (value "VDDA") (footprint "TP") (libsource (lib "*") (part "TP")))
    (comp (ref "U3")
      (value "STM32F4")
      (footprint "BGA216_0R8_13X13_SKT")
      (libsource (lib "mb1045") (part "Big_Manta_TFBGA216"))
    )
    (comp (ref "X1")
      (value "CM200C32.768KDZF")
      (footprint "XTAL_4SM_8X3R8")
      (libsource (lib "*") (part "MC306"))
    )
    (comp (ref "X2")
      (value "25MHz(with socket)")
      (footprint "XTAL_socket")
      (description "Crystal")
      (libsource (lib "*") (part "CRYSTAL"))
    )
  )
  (nets
    (net (code "1") (name "+3V3") (class "Default")
      (node (ref "JP8") (pin "1") (pintype "passive"))
      (node (ref "R22") (pin "2") (pinfunction "2_2") (pintype "passive"))
      (node (ref "SW1") (pin "1") (pintype "passive"))
      (node (ref "SW2") (pin "1") (pintype "passive"))
    )
    (net (code "2") (name "/A0") (class "Default")
      (node (ref "R231") (pin "2") (pinfunction "2_2") (pintype "passive"))
    )
    (net (code "3") (name "/A1") (class "Default")
      (node (ref "R226") (pin "2") (pinfunction "2_2") (pintype "passive"))
    )
    (net (code "4") (name "/A2") (class "Default")
      (node (ref "R224") (pin "2") (pinfunction "2_2") (pintype "passive"))
    )
    (net (code "5") (name "/A3") (class "Default")
      (node (ref "R221") (pin "2") (pinfunction "2_2") (pintype "passive"))
    )
    (net (code "6") (name "/A4") (class "Default")
      (node (ref "R217") (pin "2") (pinfunction "2_2") (pintype "passive"))
    )
    (net (code "7") (name "/A5") (class "Default")
      (node (ref "R213") (pin "2") (pinfunction "2_2") (pintype "passive"))
    )
    (net (code "8") (name "/A6") (class "Default")
      (node (ref "R253") (pin "2") (pinfunction "2_2") (pintype "passive"))
    )
    (net (code "9") (name "/A7") (class "Default")
      (node (ref "R250") (pin "2") (pinfunction "2_2") (pintype "passive"))
    )
    (net (code "10") (name "/A8") (class "Default")
      (node (ref "R254") (pin "2") (pinfunction "2_2") (pintype "passive"))
    )
    (net (code "11") (name "/A9") (class "Default")
      (node (ref "R273") (pin "2") (pinfunction "2_2") (pintype "passive"))
    )
    (net (code "12") (name "/A10") (class "Default")
      (node (ref "R258") (pin "2") (pinfunction "2_2") (pintype "passive"))
    )
    (net (code "13") (name "/A11") (class "Default")
      (node (ref "R257") (pin "2") (pinfunction "2_2") (pintype "passive"))
    )
    (net (code "14") (name "/A12") (class "Default")
      (node (ref "R285") (pin "2") (pinfunction "2_2") (pintype "passive"))
    )
    (net (code "15") (name "/A13") (class "Default")
      (node (ref "R269") (pin "2") (pinfunction "2_2") (pintype "passive"))
    )
    (net (code "16") (name "/A14") (class "Default")
      (node (ref "R286") (pin "2") (pinfunction "2_2") (pintype "passive"))
    )
    (net (code "17") (name "/A15") (class "Default")
      (node (ref "R271") (pin "2") (pinfunction "2_2") (pintype "passive"))
    )
    (net (code "18") (name "/A16") (class "Default")
      (node (ref "R272") (pin "1") (pinfunction "1_1") (pintype "passive"))
    )
    (net (code "19") (name "/A17") (class "Default")
      (node (ref "R287") (pin "2") (pinfunction "2_2") (pintype "passive"))
    )
    (net (code "20") (name "/A18") (class "Default")
      (node (ref "R270") (pin "2") (pinfunction "2_2") (pintype "passive"))
    )
    (net (code "21") (name "/A19") (class "Default")
      (node (ref "R36") (pin "2") (pinfunction "2_2") (pintype "passive"))
      (node (ref "R37") (pin "2") (pinfunction "2_2") (pintype "passive"))
    )
    (net (code "22") (name "/A20") (class "Default")
      (node (ref "R34") (pin "2") (pinfunction "2_2") (pintype "passive"))
      (node (ref "R35") (pin "2") (pinfunction "2_2") (pintype "passive"))
    )
    (net (code "23") (name "/A21") (class "Default")
      (node (ref "R24") (pin "2") (pinfunction "2_2") (pintype "passive"))
      (node (ref "R29") (pin "2") (pinfunction "2_2") (pintype "passive"))
    )
    (net (code "24") (name "/A22") (class "Default")
      (node (ref "R30") (pin "2") (pinfunction "2_2") (pintype "passive"))
      (node (ref "R32") (pin "2") (pinfunction "2_2") (pintype "passive"))
    )
    (net (code "25") (name "/A23") (class "Default")
      (node (ref "R40") (pin "2") (pinfunction "2_2") (pintype "passive"))
      (node (ref "R41") (pin "2") (pinfunction "2_2") (pintype "passive"))
    )
    (net (code "27") (name "/BOOT0") (class "Default")
      (node (ref "SW1") (pin "2") (pintype "passive"))
      (node (ref "U3") (pin "E6") (pinfunction "BOOT0_E6") (pintype "passive"))
    )
    (net (code "28") (name "/CAN1_RX") (class "Default")
      (node (ref "JP16") (pin "2") (pinfunction "NO_2") (pintype "passive"))
    )
    (net (code "29") (name "/CAN1_TX") (class "Default")
      (node (ref "R256") (pin "2") (pinfunction "2_2") (pintype "passive"))
    )
    (net (code "30") (name "/D0") (class "Default")
      (node (ref "R74") (pin "2") (pinfunction "2_2") (pintype "passive"))
    )
    (net (code "31") (name "/D1") (class "Default")
      (node (ref "R61") (pin "2") (pinfunction "2_2") (pintype "passive"))
    )
    (net (code "32") (name "/D2") (class "Default")
      (node (ref "R274") (pin "2") (pinfunction "2_2") (pintype "passive"))
    )
    (net (code "33") (name "/D3") (class "Default")
      (node (ref "R288") (pin "2") (pinfunction "2_2") (pintype "passive"))
    )
    (net (code "34") (name "/D4") (class "Default")
      (node (ref "R65") (pin "2") (pinfunction "2_2") (pintype "passive"))
    )
    (net (code "35") (name "/D5") (class "Default")
      (node (ref "R54") (pin "2") (pinfunction "2_2") (pintype "passive"))
    )
    (net (code "36") (name "/D6") (class "Default")
      (node (ref "R53") (pin "2") (pinfunction "2_2") (pintype "passive"))
    )
    (net (code "37") (name "/D7") (class "Default")
      (node (ref "R66") (pin "2") (pinfunction "2_2") (pintype "passive"))
    )
    (net (code "38") (name "/D8") (class "Default")
      (node (ref "R55") (pin "2") (pinfunction "2_2") (pintype "passive"))
    )
    (net (code "39") (name "/D9") (class "Default")
      (node (ref "R67") (pin "2") (pinfunction "2_2") (pintype "passive"))
    )
    (net (code "40") (name "/D10") (class "Default")
      (node (ref "R69") (pin "2") (pinfunction "2_2") (pintype "passive"))
    )
    (net (code "41") (name "/D11") (class "Default")
      (node (ref "R56") (pin "2") (pinfunction "2_2") (pintype "passive"))
    )
    (net (code "42") (name "/D12") (class "Default")
      (node (ref "R68") (pin "2") (pinfunction "2_2") (pintype "passive"))
    )
    (net (code "43") (name "/D13") (class "Default")
      (node (ref "R60") (pin "2") (pinfunction "2_2") (pintype "passive"))
    )
    (net (code "44") (name "/D14") (class "Default")
      (node (ref "R72") (pin "2") (pinfunction "2_2") (pintype "passive"))
    )
    (net (code "45") (name "/D15") (class "Default")
      (node (ref "R73") (pin "2") (pinfunction "2_2") (pintype "passive"))
    )
    (net (code "46") (name "/D16") (class "Default")
      (node (ref "R57") (pin "1") (pinfunction "1_1") (pintype "passive"))
    )
    (net (code "47") (name "/D17") (class "Default")
      (node (ref "R58") (pin "1") (pinfunction "1_1") (pintype "passive"))
    )
    (net (code "48") (name "/D18") (class "Default")
      (node (ref "R70") (pin "1") (pinfunction "1_1") (pintype "passive"))
    )
    (net (code "49") (name "/D19") (class "Default")
      (node (ref "R71") (pin "1") (pinfunction "1_1") (pintype "passive"))
    )
    (net (code "50") (name "/D20") (class "Default")
      (node (ref "R59") (pin "1") (pinfunction "1_1") (pintype "passive"))
    )
    (net (code "51") (name "/D21") (class "Default")
      (node (ref "R278") (pin "1") (pinfunction "1_1") (pintype "passive"))
    )
    (net (code "52") (name "/D22") (class "Default")
      (node (ref "R291") (pin "1") (pinfunction "1_1") (pintype "passive"))
    )
    (net (code "53") (name "/D23") (class "Default")
      (node (ref "R290") (pin "1") (pinfunction "1_1") (pintype "passive"))
    )
    (net (code "54") (name "/D24") (class "Default")
      (node (ref "R277") (pin "1") (pinfunction "1_1") (pintype "passive"))
    )
    (net (code "55") (name "/D25") (class "Default")
      (node (ref "R276") (pin "1") (pinfunction "1_1") (pintype "passive"))
    )
    (net (code "56") (name "/D26") (class "Default")
      (node (ref "R275") (pin "1") (pinfunction "1_1") (pintype "passive"))
    )
    (net (code "57") (name "/D27") (class "Default")
      (node (ref "R289") (pin "1") (pinfunction "1_1") (pintype "passive"))
    )
    (net (code "58") (name "/D28") (class "Default")
      (node (ref "R247") (pin "1") (pinfunction "1_1") (pintype "passive"))
    )
    (net (code "59") (name "/D29") (class "Default")
      (node (ref "R237") (pin "1") (pinfunction "1_1") (pintype "passive"))
    )
    (net (code "60") (name "/D30") (class "Default")
      (node (ref "R241") (pin "1") (pinfunction "1_1") (pintype "passive"))
    )
    (net (code "61") (name "/D31") (class "Default")
      (node (ref "R244") (pin "1") (pinfunction "1_1") (pintype "passive"))
    )
    (net (code "63") (name "/FMC_NWAIT") (class "Default") (node (ref "JP5") (pin "1") (pintype "passive")))
    (net (code "64") (name "/I2S3_SD") (class "Default") (node (ref "JP5") (pin "3") (pintype "passive")))
    (net (code "65") (name "/LCD_BL_CTRL") (class "Default")
      (node (ref "R283") (pin "2") (pinfunction "2_2") (pintype "passive"))
    )
    (net (code "67") (name "/LCD_G0") (class "Default")
      (node (ref "U3") (pin "J12") (pinfunction "PJ7_J12") (pintype "passive"))
    )
    (net (code "68") (name "/LCD_G1") (class "Default")
      (node (ref "U3") (pin "H12") (pinfunction "PJ8_H12") (pintype "passive"))
    )
    (net (code "69") (name "/LCD_G2") (class "Default")
      (node (ref "U3") (pin "J13") (pinfunction "PJ9_J13") (pintype "passive"))
    )
    (net (code "70") (name "/LCD_G3") (class "Default")
      (node (ref "U3") (pin "H13") (pinfunction "PJ10_H13") (pintype "passive"))
    )
    (net (code "71") (name "/LCD_G4") (class "Default")
      (node (ref "U3") (pin "G12") (pinfunction "PJ11_G12") (pintype "passive"))
    )
    (net (code "72") (name "/LCD_G5") (class "Default")
      (node (ref "U3") (pin "G13") (pinfunction "PK0_G13") (pintype "passive"))
    )
    (net (code "73") (name "/LCD_G6") (class "Default")
      (node (ref "U3") (pin "F12") (pinfunction "PK1_F12") (pintype "passive"))
    )
    (net (code "74") (name "/LCD_G7") (class "Default")
      (node (ref "U3") (pin "F13") (pinfunction "PK2_F13") (pintype "passive"))
    )
    (net (code "76") (name "/LCD_R0") (class "Default")
      (node (ref "U3") (pin "G4") (pinfunction "PI15_G4") (pintype "passive"))
    )
    (net (code "77") (name "/LCD_R1") (class "Default")
      (node (ref "U3") (pin "R6") (pinfunction "PJ0_R6") (pintype "passive"))
    )
    (net (code "78") (name "/LCD_R2") (class "Default")
      (node (ref "U3") (pin "R7") (pinfunction "PJ1_R7") (pintype "passive"))
    )
    (net (code "79") (name "/LCD_R3") (class "Default")
      (node (ref "U3") (pin "P7") (pinfunction "PJ2_P7") (pintype "passive"))
    )
    (net (code "80") (name "/LCD_R4") (class "Default")
      (node (ref "U3") (pin "N8") (pinfunction "PJ3_N8") (pintype "passive"))
    )
    (net (code "81") (name "/LCD_R5") (class "Default")
      (node (ref "U3") (pin "M9") (pinfunction "PJ4_M9") (pintype "passive"))
    )
    (net (code "82") (name "/LCD_R6") (class "Default")
      (node (ref "U3") (pin "M14") (pinfunction "PJ5_M14") (pintype "passive"))
    )
    (net (code "83") (name "/LCD_R7") (class "Default")
      (node (ref "U3") (pin "K12") (pinfunction "PJ6_K12") (pintype "passive"))
    )
    (net (code "85") (name "/MC_BusVoltage") (class "Default")
      (node (ref "R235") (pin "1") (pinfunction "1_1") (pintype "passive"))
    )
    (net (code "86") (name "/MC_CurrentA") (class "Default")
      (node (ref "R218") (pin "1") (pinfunction "1_1") (pintype "passive"))
    )
    (net (code "87") (name "/MC_CurrentB") (class "Default")
      (node (ref "R232") (pin "1") (pinfunction "1_1") (pintype "passive"))
    )
    (net (code "88") (name "/MC_CurrentC") (class "Default")
      (node (ref "R242") (pin "1") (pinfunction "1_1") (pintype "passive"))
    )
    (net (code "89") (name "/MC_DissipativeBrake") (class "Default")
      (node (ref "R240") (pin "1") (pinfunction "1_1") (pintype "passive"))
    )
    (net (code "90") (name "/MC_EnA") (class "Default")
      (node (ref "R223") (pin "2") (pinfunction "2_2") (pintype "passive"))
    )
    (net (code "91") (name "/MC_EnB") (class "Default")
      (node (ref "R210") (pin "2") (pinfunction "2_2") (pintype "passive"))
    )
    (net (code "92") (name "/MC_EnIndex") (class "Default")
      (node (ref "R215") (pin "2") (pinfunction "2_2") (pintype "passive"))
    )
    (net (code "93") (name "/MC_Heatsink") (class "Default")
      (node (ref "R263") (pin "1") (pinfunction "1_1") (pintype "passive"))
    )
    (net (code "94") (name "/MC_NTC") (class "Default")
      (node (ref "R246") (pin "2") (pinfunction "2_2") (pintype "passive"))
    )
    (net (code "95") (name "/MC_PFCpwm") (class "Default")
      (node (ref "R255") (pin "2") (pinfunction "2_2") (pintype "passive"))
    )
    (net (code "96") (name "/MC_PFCsync1") (class "Default")
      (node (ref "R268") (pin "2") (pinfunction "2_2") (pintype "passive"))
    )
    (net (code "97") (name "/MC_PFCsync2") (class "Default")
      (node (ref "R252") (pin "2") (pinfunction "2_2") (pintype "passive"))
    )
    (net (code "98") (name "/MC_UH") (class "Default")
      (node (ref "R292") (pin "1") (pinfunction "1_1") (pintype "passive"))
    )
    (net (code "99") (name "/MC_UL") (class "Default")
      (node (ref "R225") (pin "2") (pinfunction "2_2") (pintype "passive"))
    )
    (net (code "100") (name "/MC_VL") (class "Default")
      (node (ref "R282") (pin "1") (pinfunction "1_1") (pintype "passive"))
    )
    (net (code "101") (name "/MC_WH") (class "Default")
      (node (ref "R280") (pin "1") (pinfunction "1_1") (pintype "passive"))
    )
    (net (code "102") (name "/MC_WL") (class "Default")
      (node (ref "R234") (pin "1") (pinfunction "1_1") (pintype "passive"))
    )
    (net (code "103") (name "/MIC_CK") (class "Default")
      (node (ref "R45") (pin "2") (pinfunction "2_2") (pintype "passive"))
    )
    (net (code "104") (name "/MII_COL") (class "Default")
      (node (ref "SB8") (pin "2") (pinfunction "2_2") (pintype "passive"))
    )
    (net (code "105") (name "/MII_CRS") (class "Default")
      (node (ref "SB7") (pin "1") (pinfunction "1_1") (pintype "passive"))
    )
    (net (code "106") (name "/MII_MCO") (class "Default")
      (node (ref "R279") (pin "2") (pinfunction "2_2") (pintype "passive"))
    )
    (net (code "107") (name "/MII_MDC") (class "Default")
      (node (ref "R222") (pin "1") (pinfunction "1_1") (pintype "passive"))
    )
    (net (code "108") (name "/MII_MDIO") (class "Default")
      (node (ref "R211") (pin "2") (pinfunction "2_2") (pintype "passive"))
    )
    (net (code "109") (name "/MII_RXD0") (class "Default")
      (node (ref "R239") (pin "1") (pinfunction "1_1") (pintype "passive"))
    )
    (net (code "110") (name "/MII_RXD1") (class "Default")
      (node (ref "R267") (pin "1") (pinfunction "1_1") (pintype "passive"))
    )
    (net (code "111") (name "/MII_RX_CLK") (class "Default")
      (node (ref "R214") (pin "2") (pinfunction "2_2") (pintype "passive"))
    )
    (net (code "112") (name "/MII_RX_DV") (class "Default")
      (node (ref "R227") (pin "2") (pinfunction "2_2") (pintype "passive"))
    )
    (net (code "113") (name "/MII_RX_ER") (class "Default")
      (node (ref "R43") (pin "1") (pinfunction "1_1") (pintype "passive"))
    )
    (net (code "114") (name "/MII_TXD0") (class "Default")
      (node (ref "R233") (pin "2") (pinfunction "2_2") (pintype "passive"))
    )
    (net (code "115") (name "/MII_TXD1") (class "Default")
      (node (ref "R236") (pin "2") (pinfunction "2_2") (pintype "passive"))
    )
    (net (code "116") (name "/MII_TXD2") (class "Default")
      (node (ref "R228") (pin "1") (pinfunction "1_1") (pintype "passive"))
    )
    (net (code "117") (name "/MII_TXD3") (class "Default")
      (node (ref "R243") (pin "1") (pinfunction "1_1") (pintype "passive"))
    )
    (net (code "118") (name "/MII_TX_CLK") (class "Default")
      (node (ref "R238") (pin "1") (pinfunction "1_1") (pintype "passive"))
    )
    (net (code "119") (name "/MII_TX_EN") (class "Default")
      (node (ref "R249") (pin "2") (pinfunction "2_2") (pintype "passive"))
    )
    (net (code "120") (name "/PA0") (class "Default")
      (node (ref "R219") (pin "1") (pinfunction "1_1") (pintype "passive"))
      (node (ref "R223") (pin "1") (pinfunction "1_1") (pintype "passive"))
      (node (ref "SB7") (pin "2") (pinfunction "2_2") (pintype "passive"))
      (node (ref "U3") (pin "N3") (pinfunction "PA0-WKUP_N3") (pintype "passive"))
    )
    (net (code "121") (name "/PA1") (class "Default")
      (node (ref "R210") (pin "1") (pinfunction "1_1") (pintype "passive"))
      (node (ref "R214") (pin "1") (pinfunction "1_1") (pintype "passive"))
      (node (ref "U3") (pin "N2") (pinfunction "PA1_N2") (pintype "passive"))
    )
    (net (code "122") (name "/PA2") (class "Default")
      (node (ref "R211") (pin "1") (pinfunction "1_1") (pintype "passive"))
      (node (ref "R215") (pin "1") (pinfunction "1_1") (pintype "passive"))
      (node (ref "U3") (pin "P2") (pinfunction "PA2_P2") (pintype "passive"))
    )
    (net (code "123") (name "/PA3") (class "Default")
      (node (ref "U3") (pin "R2") (pinfunction "PA3_R2") (pintype "passive"))
    )
    (net (code "124") (name "/PA4") (class "Default")
      (node (ref "U3") (pin "N4") (pinfunction "PA4_N4") (pintype "passive"))
    )
    (net (code "125") (name "/PA5") (class "Default")
      (node (ref "U3") (pin "P4") (pinfunction "PA5_P4") (pintype "passive"))
    )
    (net (code "126") (name "/PA6") (class "Default")
      (node (ref "U3") (pin "P3") (pinfunction "PA6_P3") (pintype "passive"))
    )
    (net (code "127") (name "/PA7") (class "Default")
      (node (ref "R225") (pin "1") (pinfunction "1_1") (pintype "passive"))
      (node (ref "R227") (pin "1") (pinfunction "1_1") (pintype "passive"))
      (node (ref "U3") (pin "R3") (pinfunction "PA7_R3") (pintype "passive"))
    )
    (net (code "128") (name "/PA8") (class "Default")
      (node (ref "R268") (pin "1") (pinfunction "1_1") (pintype "passive"))
      (node (ref "R279") (pin "1") (pinfunction "1_1") (pintype "passive"))
      (node (ref "R283") (pin "1") (pinfunction "1_1") (pintype "passive"))
      (node (ref "U3") (pin "F15") (pinfunction "PA8_F15") (pintype "passive"))
    )
    (net (code "129") (name "/PA9") (class "Default")
      (node (ref "R262") (pin "1") (pinfunction "1_1") (pintype "passive"))
      (node (ref "R266") (pin "1") (pinfunction "1_1") (pintype "passive"))
      (node (ref "U3") (pin "E15") (pinfunction "PA9_E15") (pintype "passive"))
    )
    (net (code "130") (name "/PA10") (class "Default")
      (node (ref "U3") (pin "D15") (pinfunction "PA10_D15") (pintype "passive"))
    )
    (net (code "131") (name "/PA11") (class "Default")
      (node (ref "JP16") (pin "1") (pinfunction "COMMON_1") (pintype "passive"))
      (node (ref "R255") (pin "1") (pinfunction "1_1") (pintype "passive"))
      (node (ref "U3") (pin "C15") (pinfunction "PA11_C15") (pintype "passive"))
    )
    (net (code "132") (name "/PA12") (class "Default")
      (node (ref "R252") (pin "1") (pinfunction "1_1") (pintype "passive"))
      (node (ref "R256") (pin "1") (pinfunction "1_1") (pintype "passive"))
      (node (ref "R261") (pin "1") (pinfunction "1_1") (pintype "passive"))
      (node (ref "U3") (pin "B15") (pinfunction "PA12_B15") (pintype "passive"))
    )
    (net (code "133") (name "/PA13") (class "Default")
      (node (ref "U3") (pin "A15") (pinfunction "PA13_A15") (pintype "passive"))
    )
    (net (code "134") (name "/PA14") (class "Default")
      (node (ref "U3") (pin "A14") (pinfunction "PA14_A14") (pintype "passive"))
    )
    (net (code "135") (name "/PA15") (class "Default")
      (node (ref "U3") (pin "A13") (pinfunction "PA15_A13") (pintype "passive"))
    )
    (net (code "136") (name "/PAR_D7") (class "Default")
      (node (ref "R114") (pin "1") (pinfunction "1_1") (pintype "passive"))
    )
    (net (code "139") (name "/PB0") (class "Default")
      (node (ref "R282") (pin "2") (pinfunction "2_2") (pintype "passive"))
      (node (ref "U3") (pin "R5") (pinfunction "PB0_R5") (pintype "passive"))
    )
    (net (code "140") (name "/PB1") (class "Default")
      (node (ref "R234") (pin "2") (pinfunction "2_2") (pintype "passive"))
      (node (ref "U3") (pin "R4") (pinfunction "PB1_R4") (pintype "passive"))
    )
    (net (code "141") (name "/PB2") (class "Default")
      (node (ref "R5") (pin "2") (pinfunction "2_2") (pintype "passive"))
      (node (ref "U3") (pin "M5") (pinfunction "PB2_M5") (pintype "passive"))
    )
    (net (code "142") (name "/PB3") (class "Default")
      (node (ref "JP4") (pin "2") (pintype "passive"))
      (node (ref "U3") (pin "A10") (pinfunction "PB3_A10") (pintype "passive"))
    )
    (net (code "143") (name "/PB4") (class "Default")
      (node (ref "U3") (pin "A9") (pinfunction "PB4_A9") (pintype "passive"))
    )
    (net (code "144") (name "/PB5") (class "Default")
      (node (ref "U3") (pin "A8") (pinfunction "PB5_A8") (pintype "passive"))
    )
    (net (code "145") (name "/PB6") (class "Default")
      (node (ref "U3") (pin "B6") (pinfunction "PB6_B6") (pintype "passive"))
    )
    (net (code "146") (name "/PB7") (class "Default")
      (node (ref "U3") (pin "B5") (pinfunction "PB7_B5") (pintype "passive"))
    )
    (net (code "147") (name "/PB8") (class "Default")
      (node (ref "R240") (pin "2") (pinfunction "2_2") (pintype "passive"))
      (node (ref "R243") (pin "2") (pinfunction "2_2") (pintype "passive"))
      (node (ref "U3") (pin "A7") (pinfunction "PB8_A7") (pintype "passive"))
    )
    (net (code "148") (name "/PB9") (class "Default")
      (node (ref "U3") (pin "B4") (pinfunction "PB9_B4") (pintype "passive"))
    )
    (net (code "149") (name "/PB10") (class "Default")
      (node (ref "U3") (pin "P12") (pinfunction "PB10_P12") (pintype "passive"))
    )
    (net (code "150") (name "/PB11") (class "Default")
      (node (ref "U3") (pin "R13") (pinfunction "PB11_R13") (pintype "passive"))
    )
    (net (code "151") (name "/PB12") (class "Default")
      (node (ref "R260") (pin "2") (pinfunction "2_2") (pintype "passive"))
      (node (ref "U3") (pin "L13") (pinfunction "PB12_L13") (pintype "passive"))
    )
    (net (code "152") (name "/PB13") (class "Default")
      (node (ref "R264") (pin "2") (pinfunction "2_2") (pintype "passive"))
      (node (ref "U3") (pin "K14") (pinfunction "PB13_K14") (pintype "passive"))
    )
    (net (code "153") (name "/PB14") (class "Default")
      (node (ref "U3") (pin "R14") (pinfunction "PB14_R14") (pintype "passive"))
    )
    (net (code "154") (name "/PB15") (class "Default")
      (node (ref "U3") (pin "R15") (pinfunction "PB15_R15") (pintype "passive"))
    )
    (net (code "156") (name "/PC0") (class "Default")
      (node (ref "U3") (pin "M2") (pinfunction "PC0_M2") (pintype "passive"))
    )
    (net (code "157") (name "/PC1") (class "Default")
      (node (ref "R218") (pin "2") (pinfunction "2_2") (pintype "passive"))
      (node (ref "R222") (pin "2") (pinfunction "2_2") (pintype "passive"))
      (node (ref "U3") (pin "M3") (pinfunction "PC1_M3") (pintype "passive"))
    )
    (net (code "158") (name "/PC2") (class "Default")
      (node (ref "R228") (pin "2") (pinfunction "2_2") (pintype "passive"))
      (node (ref "R232") (pin "2") (pinfunction "2_2") (pintype "passive"))
      (node (ref "U3") (pin "M4") (pinfunction "PC2_M4") (pintype "passive"))
    )
    (net (code "159") (name "/PC3") (class "Default")
      (node (ref "R238") (pin "2") (pinfunction "2_2") (pintype "passive"))
      (node (ref "R242") (pin "2") (pinfunction "2_2") (pintype "passive"))
      (node (ref "U3") (pin "L4") (pinfunction "PC3_L4") (pintype "passive"))
    )
    (net (code "160") (name "/PC4") (class "Default")
      (node (ref "R235") (pin "2") (pinfunction "2_2") (pintype "passive"))
      (node (ref "R239") (pin "2") (pinfunction "2_2") (pintype "passive"))
      (node (ref "U3") (pin "N5") (pinfunction "PC4_N5") (pintype "passive"))
    )
    (net (code "161") (name "/PC5") (class "Default")
      (node (ref "R263") (pin "2") (pinfunction "2_2") (pintype "passive"))
      (node (ref "R267") (pin "2") (pinfunction "2_2") (pintype "passive"))
      (node (ref "U3") (pin "P5") (pinfunction "PC5_P5") (pintype "passive"))
    )
    (net (code "162") (name "/PC6") (class "Default")
      (node (ref "JP4") (pin "3") (pintype "passive"))
      (node (ref "R292") (pin "2") (pinfunction "2_2") (pintype "passive"))
      (node (ref "U3") (pin "H15") (pinfunction "PC6_H15") (pintype "passive"))
    )
    (net (code "163") (name "/PC7") (class "Default")
      (node (ref "R45") (pin "1") (pinfunction "1_1") (pintype "passive"))
      (node (ref "U3") (pin "G15") (pinfunction "PC7_G15") (pintype "passive"))
    )
    (net (code "164") (name "/PC8") (class "Default")
      (node (ref "R280") (pin "2") (pinfunction "2_2") (pintype "passive"))
      (node (ref "R281") (pin "2") (pinfunction "2_2") (pintype "passive"))
      (node (ref "U3") (pin "G14") (pinfunction "PC8_G14") (pintype "passive"))
    )
    (net (code "165") (name "/PC9") (class "Default")
      (node (ref "R265") (pin "2") (pinfunction "2_2") (pintype "passive"))
      (node (ref "U3") (pin "F14") (pinfunction "PC9_F14") (pintype "passive"))
    )
    (net (code "166") (name "/PC10") (class "Default")
      (node (ref "R293") (pin "2") (pinfunction "2_2") (pintype "passive"))
      (node (ref "U3") (pin "B14") (pinfunction "PC10_B14") (pintype "passive"))
    )
    (net (code "167") (name "/PC11") (class "Default")
      (node (ref "R284") (pin "2") (pinfunction "2_2") (pintype "passive"))
      (node (ref "U3") (pin "B13") (pinfunction "PC11_B13") (pintype "passive"))
    )
    (net (code "168") (name "/PC12") (class "Default")
      (node (ref "U3") (pin "A12") (pinfunction "PC12_A12") (pintype "passive"))
    )
    (net (code "169") (name "/PC13") (class "Default")
      (node (ref "U3") (pin "D1") (pinfunction "PC13-ANTI_TAMP_D1") (pintype "passive"))
    )
    (net (code "170") (name "/PC14") (class "Default")
      (node (ref "R19") (pin "2") (pinfunction "2_2") (pintype "passive"))
      (node (ref "U3") (pin "E1") (pinfunction "PC14-OSC32_IN_E1") (pintype "passive"))
    )
    (net (code "171") (name "/PC15") (class "Default")
      (node (ref "R18") (pin "2") (pinfunction "2_2") (pintype "passive"))
      (node (ref "U3") (pin "F1") (pinfunction "PC15-OSC32_OUT_F1") (pintype "passive"))
    )
    (net (code "173") (name "/PD2") (class "Default")
      (node (ref "R294") (pin "2") (pinfunction "2_2") (pintype "passive"))
      (node (ref "U3") (pin "D12") (pinfunction "PD2_D12") (pintype "passive"))
    )
    (net (code "174") (name "/PD3") (class "Default")
      (node (ref "U3") (pin "C11") (pinfunction "PD3_C11") (pintype "passive"))
    )
    (net (code "175") (name "/PD4") (class "Default")
      (node (ref "U3") (pin "D11") (pinfunction "PD4_D11") (pintype "passive"))
    )
    (net (code "176") (name "/PD5") (class "Default")
      (node (ref "U3") (pin "C10") (pinfunction "PD5_C10") (pintype "passive"))
    )
    (net (code "177") (name "/PD6") (class "Default")
      (node (ref "JP5") (pin "2") (pintype "passive"))
      (node (ref "U3") (pin "B11") (pinfunction "PD6_B11") (pintype "passive"))
    )
    (net (code "178") (name "/PD7") (class "Default")
      (node (ref "U3") (pin "A11") (pinfunction "PD7_A11") (pintype "passive"))
    )
    (net (code "180") (name "/PE0") (class "Default")
      (node (ref "U3") (pin "A6") (pinfunction "PE0_A6") (pintype "passive"))
    )
    (net (code "181") (name "/PE1") (class "Default")
      (node (ref "U3") (pin "A5") (pinfunction "PE1_A5") (pintype "passive"))
    )
    (net (code "183") (name "/PF6") (class "Default")
      (node (ref "U3") (pin "K2") (pinfunction "PF6_K2") (pintype "passive"))
    )
    (net (code "184") (name "/PF7") (class "Default")
      (node (ref "U3") (pin "K1") (pinfunction "PF7_K1") (pintype "passive"))
    )
    (net (code "185") (name "/PF8") (class "Default")
      (node (ref "U3") (pin "L3") (pinfunction "PF8_L3") (pintype "passive"))
    )
    (net (code "186") (name "/PF9") (class "Default")
      (node (ref "U3") (pin "L2") (pinfunction "PF9_L2") (pintype "passive"))
    )
    (net (code "187") (name "/PF10") (class "Default")
      (node (ref "U3") (pin "L1") (pinfunction "PF10_L1") (pintype "passive"))
    )
    (net (code "188") (name "/PF11") (class "Default")
      (node (ref "R52") (pin "2") (pinfunction "2_2") (pintype "passive"))
    )
    (net (code "190") (name "/PG6") (class "Default")
      (node (ref "U3") (pin "J15") (pinfunction "PG6_J15") (pintype "passive"))
    )
    (net (code "191") (name "/PG7") (class "Default")
      (node (ref "U3") (pin "J14") (pinfunction "PG7_J14") (pintype "passive"))
    )
    (net (code "192") (name "/PG8") (class "Default")
      (node (ref "R62") (pin "2") (pinfunction "2_2") (pintype "passive"))
    )
    (net (code "193") (name "/PG9") (class "Default")
      (node (ref "U3") (pin "D9") (pinfunction "PG9_D9") (pintype "passive"))
    )
    (net (code "194") (name "/PG10") (class "Default")
      (node (ref "U3") (pin "C8") (pinfunction "PG10_C8") (pintype "passive"))
    )
    (net (code "195") (name "/PG11") (class "Default")
      (node (ref "R246") (pin "1") (pinfunction "1_1") (pintype "passive"))
      (node (ref "R249") (pin "1") (pinfunction "1_1") (pintype "passive"))
      (node (ref "U3") (pin "B8") (pinfunction "PG11_B8") (pintype "passive"))
    )
    (net (code "196") (name "/PG12") (class "Default")
      (node (ref "U3") (pin "C7") (pinfunction "PG12_C7") (pintype "passive"))
    )
    (net (code "197") (name "/PG13") (class "Default")
      (node (ref "R233") (pin "1") (pinfunction "1_1") (pintype "passive"))
      (node (ref "U3") (pin "B3") (pinfunction "PG13_B3") (pintype "passive"))
    )
    (net (code "198") (name "/PG14") (class "Default")
      (node (ref "R236") (pin "1") (pinfunction "1_1") (pintype "passive"))
      (node (ref "U3") (pin "A4") (pinfunction "PG14_A4") (pintype "passive"))
    )
    (net (code "199") (name "/PG15") (class "Default")
      (node (ref "R42") (pin "2") (pinfunction "2_2") (pintype "passive"))
    )
    (net (code "201") (name "/PH0") (class "Default")
      (node (ref "R20") (pin "1") (pinfunction "1_1") (pintype "passive"))
      (node (ref "U3") (pin "G1") (pinfunction "PH0-OSC_IN_G1") (pintype "passive"))
    )
    (net (code "202") (name "/PH1") (class "Default")
      (node (ref "C23") (pin "1") (pinfunction "1_1") (pintype "passive"))
      (node (ref "U3") (pin "H1") (pinfunction "PH1-OSC_OUT_H1") (pintype "passive"))
      (node (ref "X2") (pin "1") (pinfunction "1_1") (pintype "passive"))
    )
    (net (code "203") (name "/PH2") (class "Default")
      (node (ref "U3") (pin "K4") (pinfunction "PH2_K4") (pintype "passive"))
    )
    (net (code "204") (name "/PH3") (class "Default")
      (node (ref "R248") (pin "1") (pinfunction "1_1") (pintype "passive"))
    )
    (net (code "205") (name "/PH4") (class "Default")
      (node (ref "U3") (pin "H4") (pinfunction "PH4_H4") (pintype "passive"))
    )
    (net (code "206") (name "/PH5") (class "Default")
      (node (ref "R251") (pin "1") (pinfunction "1_1") (pintype "passive"))
    )
    (net (code "207") (name "/PH6") (class "Default")
      (node (ref "U3") (pin "P13") (pinfunction "PH6_P13") (pintype "passive"))
    )
    (net (code "208") (name "/PH7") (class "Default")
      (node (ref "U3") (pin "N13") (pinfunction "PH7_N13") (pintype "passive"))
    )
    (net (code "210") (name "/PI4") (class "Default")
      (node (ref "U3") (pin "C3") (pinfunction "PI4_C3") (pintype "passive"))
    )
    (net (code "211") (name "/PI5") (class "Default")
      (node (ref "U3") (pin "D3") (pinfunction "PI5_D3") (pintype "passive"))
    )
    (net (code "212") (name "/PI8") (class "Default")
      (node (ref "U3") (pin "C2") (pinfunction "PI8-ANTI_TAMP2_C2") (pintype "passive"))
    )
    (net (code "213") (name "/PI11") (class "Default")
      (node (ref "U3") (pin "F3") (pinfunction "PI11_F3") (pintype "passive"))
    )
    (net (code "214") (name "/PI12") (class "Default")
      (node (ref "U3") (pin "E3") (pinfunction "PI12_E3") (pintype "passive"))
    )
    (net (code "215") (name "/PI13") (class "Default")
      (node (ref "U3") (pin "G3") (pinfunction "PI13_G3") (pintype "passive"))
    )
    (net (code "216") (name "/PI14") (class "Default")
      (node (ref "R295") (pin "1") (pinfunction "1_1") (pintype "passive"))
    )
    (net (code "218") (name "/PJ12") (class "Default")
      (node (ref "U3") (pin "B10") (pinfunction "PJ12_B10") (pintype "passive"))
    )
    (net (code "219") (name "/PJ13") (class "Default")
      (node (ref "U3") (pin "B9") (pinfunction "PJ13_B9") (pintype "passive"))
    )
    (net (code "220") (name "/PJ14") (class "Default")
      (node (ref "U3") (pin "C9") (pinfunction "PJ14_C9") (pintype "passive"))
    )
    (net (code "221") (name "/PJ15") (class "Default")
      (node (ref "U3") (pin "D10") (pinfunction "PJ15_D10") (pintype "passive"))
    )
    (net (code "223") (name "/PK3") (class "Default")
      (node (ref "U3") (pin "D8") (pinfunction "PK3_D8") (pintype "passive"))
    )
    (net (code "224") (name "/PK4") (class "Default")
      (node (ref "U3") (pin "D7") (pinfunction "PK4_D7") (pintype "passive"))
    )
    (net (code "225") (name "/PK5") (class "Default")
      (node (ref "U3") (pin "C6") (pinfunction "PK5_C6") (pintype "passive"))
    )
    (net (code "226") (name "/PK6") (class "Default")
      (node (ref "U3") (pin "C5") (pinfunction "PK6_C5") (pintype "passive"))
    )
    (net (code "227") (name "/PK7") (class "Default")
      (node (ref "U3") (pin "C4") (pinfunction "PK7_C4") (pintype "passive"))
    )
    (net (code "229") (name "/RESET#") (class "Default")
      (node (ref "B1") (pin "2") (pinfunction "B0_2") (pintype "passive"))
      (node (ref "B1") (pin "3") (pinfunction "B1_3") (pintype "passive"))
      (node (ref "C91") (pin "2") (pinfunction "2_2") (pintype "passive"))
      (node (ref "U3") (pin "J1") (pinfunction "NRST_J1") (pintype "passive"))
    )
    (net (code "230") (name "/RS232{slash}IrDA_TX") (class "Default")
      (node (ref "R262") (pin "2") (pinfunction "2_2") (pintype "passive"))
    )
    (net (code "231") (name "/SAI1_SDA") (class "Default")
      (node (ref "R120") (pin "2") (pinfunction "2_2") (pintype "passive"))
    )
    (net (code "232") (name "/TDO{slash}SWO") (class "Default")
      (node (ref "JP4") (pin "1") (pintype "passive"))
    )
    (net (code "233") (name "/TRACE_CK") (class "Default")
      (node (ref "R38") (pin "1") (pinfunction "1_1") (pintype "passive"))
    )
    (net (code "234") (name "/TRACE_D0") (class "Default")
      (node (ref "R39") (pin "1") (pinfunction "1_1") (pintype "passive"))
    )
    (net (code "235") (name "/TRACE_D1") (class "Default")
      (node (ref "R33") (pin "1") (pinfunction "1_1") (pintype "passive"))
    )
    (net (code "236") (name "/TRACE_D2") (class "Default")
      (node (ref "R23") (pin "1") (pinfunction "1_1") (pintype "passive"))
    )
    (net (code "237") (name "/TRACE_D3") (class "Default")
      (node (ref "R128") (pin "1") (pinfunction "1_1") (pintype "passive"))
    )
    (net (code "239") (name "/USB_FS1_DP") (class "Default")
      (node (ref "R261") (pin "2") (pinfunction "2_2") (pintype "passive"))
    )
    (net (code "240") (name "/USB_FS2_ID") (class "Default")
      (node (ref "R260") (pin "1") (pinfunction "1_1") (pintype "passive"))
    )
    (net (code "241") (name "/WAKEUP") (class "Default")
      (node (ref "R219") (pin "2") (pinfunction "2_2") (pintype "passive"))
    )
    (net (code "242") (name "/uSD_CMD") (class "Default")
      (node (ref "R294") (pin "1") (pinfunction "1_1") (pintype "passive"))
    )
    (net (code "243") (name "/uSD_D0") (class "Default")
      (node (ref "R281") (pin "1") (pinfunction "1_1") (pintype "passive"))
    )
    (net (code "244") (name "/uSD_D1") (class "Default")
      (node (ref "R265") (pin "1") (pinfunction "1_1") (pintype "passive"))
    )
    (net (code "245") (name "/uSD_D2") (class "Default")
      (node (ref "R293") (pin "1") (pinfunction "1_1") (pintype "passive"))
    )
    (net (code "246") (name "/uSD_D3") (class "Default")
      (node (ref "R284") (pin "1") (pinfunction "1_1") (pintype "passive"))
    )
    (net (code "247") (name "GND") (class "Default")
      (node (ref "B1") (pin "1") (pinfunction "A0_1") (pintype "passive"))
      (node (ref "B1") (pin "4") (pinfunction "A1_4") (pintype "passive"))
      (node (ref "BT1") (pin "2") (pinfunction "-_2") (pintype "passive"))
      (node (ref "C103") (pin "2") (pinfunction "2_2") (pintype "passive"))
      (node (ref "C104") (pin "2") (pinfunction "2_2") (pintype "passive"))
      (node (ref "C105") (pin "2") (pinfunction "2_2") (pintype "passive"))
      (node (ref "C106") (pin "2") (pinfunction "2_2") (pintype "passive"))
      (node (ref "C107") (pin "1") (pinfunction "1_1") (pintype "passive"))
      (node (ref "C108") (pin "2") (pinfunction "2_2") (pintype "passive"))
      (node (ref "C109") (pin "2") (pinfunction "2_2") (pintype "passive"))
      (node (ref "C110") (pin "1") (pinfunction "1_1") (pintype "passive"))
      (node (ref "C111") (pin "2") (pinfunction "2_2") (pintype "passive"))
      (node (ref "C112") (pin "2") (pinfunction "2_2") (pintype "passive"))
      (node (ref "C113") (pin "2") (pinfunction "2_2") (pintype "passive"))
      (node (ref "C114") (pin "2") (pinfunction "2_2") (pintype "passive"))
      (node (ref "C115") (pin "2") (pinfunction "2_2") (pintype "passive"))
      (node (ref "C118") (pin "2") (pinfunction "2_2") (pintype "passive"))
      (node (ref "C119") (pin "2") (pinfunction "2_2") (pintype "passive"))
      (node (ref "C120") (pin "2") (pinfunction "2_2") (pintype "passive"))
      (node (ref "C121") (pin "2") (pinfunction "2_2") (pintype "passive"))
      (node (ref "C122") (pin "2") (pinfunction "2_2") (pintype "passive"))
      (node (ref "C123") (pin "2") (pinfunction "2_2") (pintype "passive"))
      (node (ref "C125") (pin "2") (pinfunction "2_2") (pintype "passive"))
      (node (ref "C126") (pin "2") (pinfunction "2_2") (pintype "passive"))
      (node (ref "C127") (pin "2") (pinfunction "2_2") (pintype "passive"))
      (node (ref "C128") (pin "2") (pinfunction "2_2") (pintype "passive"))
      (node (ref "C129") (pin "2") (pinfunction "2_2") (pintype "passive"))
      (node (ref "C130") (pin "2") (pinfunction "2_2") (pintype "passive"))
      (node (ref "C133") (pin "2") (pinfunction "2_2") (pintype "passive"))
      (node (ref "C20") (pin "2") (pinfunction "2_2") (pintype "passive"))
      (node (ref "C21") (pin "2") (pinfunction "2_2") (pintype "passive"))
      (node (ref "C22") (pin "2") (pinfunction "2_2") (pintype "passive"))
      (node (ref "C23") (pin "2") (pinfunction "2_2") (pintype "passive"))
      (node (ref "C32") (pin "2") (pinfunction "2_2") (pintype "passive"))
      (node (ref "C91") (pin "1") (pinfunction "1_1") (pintype "passive"))
      (node (ref "R21") (pin "2") (pinfunction "2_2") (pintype "passive"))
      (node (ref "R24") (pin "1") (pinfunction "1_1") (pintype "passive"))
      (node (ref "R245") (pin "1") (pinfunction "1_1") (pintype "passive"))
      (node (ref "R30") (pin "1") (pinfunction "1_1") (pintype "passive"))
      (node (ref "R35") (pin "1") (pinfunction "1_1") (pintype "passive"))
      (node (ref "R37") (pin "1") (pinfunction "1_1") (pintype "passive"))
      (node (ref "R41") (pin "1") (pinfunction "1_1") (pintype "passive"))
      (node (ref "SW1") (pin "3") (pintype "passive"))
      (node (ref "SW2") (pin "3") (pintype "passive"))
      (node (ref "U3") (pin "F10") (pinfunction "VSS2_F10") (pintype "passive"))
      (node (ref "U3") (pin "F2") (pinfunction "VSS13-VSS18_F2") (pintype "passive"))
      (node (ref "U3") (pin "F6") (pinfunction "VSS3_F6") (pintype "passive"))
      (node (ref "U3") (pin "F7") (pinfunction "VSS11_F7") (pintype "passive"))
      (node (ref "U3") (pin "F8") (pinfunction "VSS10_F8") (pintype "passive"))
      (node (ref "U3") (pin "F9") (pinfunction "VSS15_F9") (pintype "passive"))
      (node (ref "U3") (pin "G10") (pinfunction "VSS9_G10") (pintype "passive"))
      (node (ref "U3") (pin "G6") (pinfunction "VSS17_G6") (pintype "passive"))
      (node (ref "U3") (pin "H10") (pinfunction "VSS20_H10") (pintype "passive"))
      (node (ref "U3") (pin "H6") (pinfunction "VSS5_H6") (pintype "passive"))
      (node (ref "U3") (pin "J10") (pinfunction "VSS8_J10") (pintype "passive"))
      (node (ref "U3") (pin "J6") (pinfunction "VSS12_J6") (pintype "passive"))
      (node (ref "U3") (pin "K10") (pinfunction "VSS14_K10") (pintype "passive"))
      (node (ref "U3") (pin "K6") (pinfunction "VSS4_K6") (pintype "passive"))
      (node (ref "U3") (pin "K7") (pinfunction "VSS6_K7") (pintype "passive"))
      (node (ref "U3") (pin "K8") (pinfunction "VSS7_K8") (pintype "passive"))
      (node (ref "U3") (pin "K9") (pinfunction "VSS1_K9") (pintype "passive"))
      (node (ref "U3") (pin "L6") (pinfunction "VSS19_L6") (pintype "passive"))
      (node (ref "U3") (pin "M1") (pinfunction "VSSA_M1") (pintype "passive"))
      (node (ref "U3") (pin "N1") (pinfunction "VREF-_N1") (pintype "passive"))
    )
    (net (code "248") (name "Net-(BT1-+)") (class "Default")
      (node (ref "BT1") (pin "1") (pinfunction "+_1") (pintype "passive"))
      (node (ref "JP8") (pin "3") (pintype "passive"))
    )
    (net (code "249") (name "Net-(C20-Pad1)") (class "Default")
      (node (ref "C20") (pin "1") (pinfunction "1_1") (pintype "passive"))
      (node (ref "R20") (pin "2") (pinfunction "2_2") (pintype "passive"))
      (node (ref "X2") (pin "2") (pinfunction "2_2") (pintype "passive"))
    )
    (net (code "250") (name "Net-(C21-Pad1)") (class "Default")
      (node (ref "C21") (pin "1") (pinfunction "1_1") (pintype "passive"))
      (node (ref "R18") (pin "1") (pinfunction "1_1") (pintype "passive"))
      (node (ref "X1") (pin "4") (pinfunction "4_4") (pintype "passive"))
    )
    (net (code "251") (name "Net-(C22-Pad1)") (class "Default")
      (node (ref "C22") (pin "1") (pinfunction "1_1") (pintype "passive"))
      (node (ref "R19") (pin "1") (pinfunction "1_1") (pintype "passive"))
      (node (ref "X1") (pin "1") (pinfunction "1_1") (pintype "passive"))
    )
    (net (code "252") (name "Net-(R5-Pad1)") (class "Default")
      (node (ref "R5") (pin "1") (pinfunction "1_1") (pintype "passive"))
      (node (ref "SW2") (pin "2") (pintype "passive"))
    )
    (net (code "253") (name "Net-(U3A-PDR_ON)") (class "Default")
      (node (ref "R21") (pin "1") (pinfunction "1_1") (pintype "passive"))
      (node (ref "R22") (pin "1") (pinfunction "1_1") (pintype "passive"))
      (node (ref "U3") (pin "E5") (pinfunction "PDR_ON_E5") (pintype "passive"))
    )
    (net (code "254") (name "Net-(U3B-PD0)") (class "Default")
      (node (ref "R274") (pin "1") (pinfunction "1_1") (pintype "passive"))
      (node (ref "U3") (pin "B12") (pinfunction "PD0_B12") (pintype "passive"))
    )
    (net (code "255") (name "Net-(U3B-PD1)") (class "Default")
      (node (ref "R288") (pin "1") (pinfunction "1_1") (pintype "passive"))
      (node (ref "U3") (pin "C12") (pinfunction "PD1_C12") (pintype "passive"))
    )
    (net (code "256") (name "Net-(U3B-PD8)") (class "Default")
      (node (ref "R60") (pin "1") (pinfunction "1_1") (pintype "passive"))
      (node (ref "U3") (pin "L15") (pinfunction "PD8_L15") (pintype "passive"))
    )
    (net (code "257") (name "Net-(U3B-PD9)") (class "Default")
      (node (ref "R72") (pin "1") (pinfunction "1_1") (pintype "passive"))
      (node (ref "U3") (pin "L14") (pinfunction "PD9_L14") (pintype "passive"))
    )
    (net (code "258") (name "Net-(U3B-PD10)") (class "Default")
      (node (ref "R73") (pin "1") (pinfunction "1_1") (pintype "passive"))
      (node (ref "U3") (pin "K15") (pinfunction "PD10_K15") (pintype "passive"))
    )
    (net (code "259") (name "Net-(U3B-PD11)") (class "Default")
      (node (ref "R272") (pin "2") (pinfunction "2_2") (pintype "passive"))
      (node (ref "U3") (pin "N10") (pinfunction "PD11_N10") (pintype "passive"))
    )
    (net (code "260") (name "Net-(U3B-PD12)") (class "Default")
      (node (ref "R287") (pin "1") (pinfunction "1_1") (pintype "passive"))
      (node (ref "U3") (pin "M10") (pinfunction "PD12_M10") (pintype "passive"))
    )
    (net (code "261") (name "Net-(U3B-PD13)") (class "Default")
      (node (ref "R270") (pin "1") (pinfunction "1_1") (pintype "passive"))
      (node (ref "U3") (pin "M11") (pinfunction "PD13_M11") (pintype "passive"))
    )
    (net (code "262") (name "Net-(U3B-PD14)") (class "Default")
      (node (ref "R74") (pin "1") (pinfunction "1_1") (pintype "passive"))
      (node (ref "U3") (pin "L12") (pinfunction "PD14_L12") (pintype "passive"))
    )
    (net (code "263") (name "Net-(U3B-PD15)") (class "Default")
      (node (ref "R61") (pin "1") (pinfunction "1_1") (pintype "passive"))
      (node (ref "U3") (pin "K13") (pinfunction "PD15_K13") (pintype "passive"))
    )
    (net (code "264") (name "Net-(U3B-PE2)") (class "Default")
      (node (ref "R38") (pin "2") (pinfunction "2_2") (pintype "passive"))
      (node (ref "R40") (pin "1") (pinfunction "1_1") (pintype "passive"))
      (node (ref "U3") (pin "A3") (pinfunction "PE2_A3") (pintype "passive"))
    )
    (net (code "265") (name "Net-(U3B-PE3)") (class "Default")
      (node (ref "R36") (pin "1") (pinfunction "1_1") (pintype "passive"))
      (node (ref "R39") (pin "2") (pinfunction "2_2") (pintype "passive"))
      (node (ref "U3") (pin "A2") (pinfunction "PE3_A2") (pintype "passive"))
    )
    (net (code "266") (name "Net-(U3B-PE4)") (class "Default")
      (node (ref "R33") (pin "2") (pinfunction "2_2") (pintype "passive"))
      (node (ref "R34") (pin "1") (pinfunction "1_1") (pintype "passive"))
      (node (ref "U3") (pin "A1") (pinfunction "PE4_A1") (pintype "passive"))
    )
    (net (code "267") (name "Net-(U3B-PE5)") (class "Default")
      (node (ref "R23") (pin "2") (pinfunction "2_2") (pintype "passive"))
      (node (ref "R29") (pin "1") (pinfunction "1_1") (pintype "passive"))
      (node (ref "U3") (pin "B1") (pinfunction "PE5_B1") (pintype "passive"))
    )
    (net (code "268") (name "Net-(U3B-PE6)") (class "Default")
      (node (ref "R114") (pin "2") (pinfunction "2_2") (pintype "passive"))
      (node (ref "R120") (pin "1") (pinfunction "1_1") (pintype "passive"))
      (node (ref "R128") (pin "2") (pinfunction "2_2") (pintype "passive"))
      (node (ref "R32") (pin "1") (pinfunction "1_1") (pintype "passive"))
      (node (ref "U3") (pin "B2") (pinfunction "PE6_B2") (pintype "passive"))
    )
    (net (code "269") (name "Net-(U3B-PE7)") (class "Default")
      (node (ref "R65") (pin "1") (pinfunction "1_1") (pintype "passive"))
      (node (ref "U3") (pin "R8") (pinfunction "PE7_R8") (pintype "passive"))
    )
    (net (code "270") (name "Net-(U3B-PE8)") (class "Default")
      (node (ref "R54") (pin "1") (pinfunction "1_1") (pintype "passive"))
      (node (ref "U3") (pin "N9") (pinfunction "PE8_N9") (pintype "passive"))
    )
    (net (code "271") (name "Net-(U3B-PE9)") (class "Default")
      (node (ref "R53") (pin "1") (pinfunction "1_1") (pintype "passive"))
      (node (ref "U3") (pin "P9") (pinfunction "PE9_P9") (pintype "passive"))
    )
    (net (code "272") (name "Net-(U3B-PE10)") (class "Default")
      (node (ref "R66") (pin "1") (pinfunction "1_1") (pintype "passive"))
      (node (ref "U3") (pin "R9") (pinfunction "PE10_R9") (pintype "passive"))
    )
    (net (code "273") (name "Net-(U3B-PE11)") (class "Default")
      (node (ref "R55") (pin "1") (pinfunction "1_1") (pintype "passive"))
      (node (ref "U3") (pin "P10") (pinfunction "PE11_P10") (pintype "passive"))
    )
    (net (code "274") (name "Net-(U3B-PE12)") (class "Default")
      (node (ref "R67") (pin "1") (pinfunction "1_1") (pintype "passive"))
      (node (ref "U3") (pin "R10") (pinfunction "PE12_R10") (pintype "passive"))
    )
    (net (code "275") (name "Net-(U3B-PE13)") (class "Default")
      (node (ref "R69") (pin "1") (pinfunction "1_1") (pintype "passive"))
      (node (ref "U3") (pin "R12") (pinfunction "PE13_R12") (pintype "passive"))
    )
    (net (code "276") (name "Net-(U3B-PE14)") (class "Default")
      (node (ref "R56") (pin "1") (pinfunction "1_1") (pintype "passive"))
      (node (ref "U3") (pin "P11") (pinfunction "PE14_P11") (pintype "passive"))
    )
    (net (code "277") (name "Net-(U3B-PE15)") (class "Default")
      (node (ref "R68") (pin "1") (pinfunction "1_1") (pintype "passive"))
      (node (ref "U3") (pin "R11") (pinfunction "PE15_R11") (pintype "passive"))
    )
    (net (code "278") (name "Net-(U3B-PF0)") (class "Default")
      (node (ref "R231") (pin "1") (pinfunction "1_1") (pintype "passive"))
      (node (ref "U3") (pin "D2") (pinfunction "PF0_D2") (pintype "passive"))
    )
    (net (code "279") (name "Net-(U3B-PF1)") (class "Default")
      (node (ref "R226") (pin "1") (pinfunction "1_1") (pintype "passive"))
      (node (ref "U3") (pin "E2") (pinfunction "PF1_E2") (pintype "passive"))
    )
    (net (code "280") (name "Net-(U3B-PF2)") (class "Default")
      (node (ref "R224") (pin "1") (pinfunction "1_1") (pintype "passive"))
      (node (ref "U3") (pin "G2") (pinfunction "PF2_G2") (pintype "passive"))
    )
    (net (code "281") (name "Net-(U3B-PF3)") (class "Default")
      (node (ref "R221") (pin "1") (pinfunction "1_1") (pintype "passive"))
      (node (ref "U3") (pin "H2") (pinfunction "PF3_H2") (pintype "passive"))
    )
    (net (code "282") (name "Net-(U3B-PF4)") (class "Default")
      (node (ref "R217") (pin "1") (pinfunction "1_1") (pintype "passive"))
      (node (ref "U3") (pin "J2") (pinfunction "PF4_J2") (pintype "passive"))
    )
    (net (code "283") (name "Net-(U3B-PF5)") (class "Default")
      (node (ref "R213") (pin "1") (pinfunction "1_1") (pintype "passive"))
      (node (ref "U3") (pin "K3") (pinfunction "PF5_K3") (pintype "passive"))
    )
    (net (code "284") (name "Net-(U3B-PF11)") (class "Default")
      (node (ref "R52") (pin "1") (pinfunction "1_1") (pintype "passive"))
      (node (ref "U3") (pin "P8") (pinfunction "PF11_P8") (pintype "passive"))
    )
    (net (code "285") (name "Net-(U3B-PF12)") (class "Default")
      (node (ref "R253") (pin "1") (pinfunction "1_1") (pintype "passive"))
      (node (ref "U3") (pin "M6") (pinfunction "PF12_M6") (pintype "passive"))
    )
    (net (code "286") (name "Net-(U3B-PF13)") (class "Default")
      (node (ref "R250") (pin "1") (pinfunction "1_1") (pintype "passive"))
      (node (ref "U3") (pin "N6") (pinfunction "PF13_N6") (pintype "passive"))
    )
    (net (code "287") (name "Net-(U3B-PF14)") (class "Default")
      (node (ref "R254") (pin "1") (pinfunction "1_1") (pintype "passive"))
      (node (ref "U3") (pin "P6") (pinfunction "PF14_P6") (pintype "passive"))
    )
    (net (code "288") (name "Net-(U3B-PF15)") (class "Default")
      (node (ref "R273") (pin "1") (pinfunction "1_1") (pintype "passive"))
      (node (ref "U3") (pin "M8") (pinfunction "PF15_M8") (pintype "passive"))
    )
    (net (code "289") (name "Net-(U3B-PG0)") (class "Default")
      (node (ref "R258") (pin "1") (pinfunction "1_1") (pintype "passive"))
      (node (ref "U3") (pin "N7") (pinfunction "PG0_N7") (pintype "passive"))
    )
    (net (code "290") (name "Net-(U3B-PG1)") (class "Default")
      (node (ref "R257") (pin "1") (pinfunction "1_1") (pintype "passive"))
      (node (ref "U3") (pin "M7") (pinfunction "PG1_M7") (pintype "passive"))
    )
    (net (code "291") (name "Net-(U3B-PG2)") (class "Default")
      (node (ref "R285") (pin "1") (pinfunction "1_1") (pintype "passive"))
      (node (ref "U3") (pin "M13") (pinfunction "PG2_M13") (pintype "passive"))
    )
    (net (code "292") (name "Net-(U3B-PG3)") (class "Default")
      (node (ref "R269") (pin "1") (pinfunction "1_1") (pintype "passive"))
      (node (ref "U3") (pin "M12") (pinfunction "PG3_M12") (pintype "passive"))
    )
    (net (code "293") (name "Net-(U3B-PG4)") (class "Default")
      (node (ref "R286") (pin "1") (pinfunction "1_1") (pintype "passive"))
      (node (ref "U3") (pin "N12") (pinfunction "PG4_N12") (pintype "passive"))
    )
    (net (code "294") (name "Net-(U3B-PG5)") (class "Default")
      (node (ref "R271") (pin "1") (pinfunction "1_1") (pintype "passive"))
      (node (ref "U3") (pin "N11") (pinfunction "PG5_N11") (pintype "passive"))
    )
    (net (code "295") (name "Net-(U3B-PG8)") (class "Default")
      (node (ref "R62") (pin "1") (pinfunction "1_1") (pintype "passive"))
      (node (ref "U3") (pin "H14") (pinfunction "PG8_H14") (pintype "passive"))
    )
    (net (code "296") (name "Net-(U3B-PG15)") (class "Default")
      (node (ref "R42") (pin "1") (pinfunction "1_1") (pintype "passive"))
      (node (ref "U3") (pin "B7") (pinfunction "PG15_B7") (pintype "passive"))
    )
    (net (code "297") (name "Net-(U3B-PH3)") (class "Default")
      (node (ref "R248") (pin "2") (pinfunction "2_2") (pintype "passive"))
      (node (ref "SB8") (pin "1") (pinfunction "1_1") (pintype "passive"))
      (node (ref "U3") (pin "J4") (pinfunction "PH3_J4") (pintype "passive"))
    )
    (net (code "298") (name "Net-(U3B-PH5)") (class "Default")
      (node (ref "R251") (pin "2") (pinfunction "2_2") (pintype "passive"))
      (node (ref "U3") (pin "J3") (pinfunction "PH5_J3") (pintype "passive"))
    )
    (net (code "299") (name "Net-(U3B-PH8)") (class "Default")
      (node (ref "R57") (pin "2") (pinfunction "2_2") (pintype "passive"))
      (node (ref "U3") (pin "P14") (pinfunction "PH8_P14") (pintype "passive"))
    )
    (net (code "300") (name "Net-(U3B-PH9)") (class "Default")
      (node (ref "R58") (pin "2") (pinfunction "2_2") (pintype "passive"))
      (node (ref "U3") (pin "N14") (pinfunction "PH9_N14") (pintype "passive"))
    )
    (net (code "301") (name "Net-(U3B-PH10)") (class "Default")
      (node (ref "R70") (pin "2") (pinfunction "2_2") (pintype "passive"))
      (node (ref "U3") (pin "P15") (pinfunction "PH10_P15") (pintype "passive"))
    )
    (net (code "302") (name "Net-(U3B-PH11)") (class "Default")
      (node (ref "R71") (pin "2") (pinfunction "2_2") (pintype "passive"))
      (node (ref "U3") (pin "N15") (pinfunction "PH11_N15") (pintype "passive"))
    )
    (net (code "303") (name "Net-(U3B-PH12)") (class "Default")
      (node (ref "R59") (pin "2") (pinfunction "2_2") (pintype "passive"))
      (node (ref "U3") (pin "M15") (pinfunction "PH12_M15") (pintype "passive"))
    )
    (net (code "304") (name "Net-(U3B-PH13)") (class "Default")
      (node (ref "R278") (pin "2") (pinfunction "2_2") (pintype "passive"))
      (node (ref "U3") (pin "E12") (pinfunction "PH13_E12") (pintype "passive"))
    )
    (net (code "305") (name "Net-(U3B-PH14)") (class "Default")
      (node (ref "R291") (pin "2") (pinfunction "2_2") (pintype "passive"))
      (node (ref "U3") (pin "E13") (pinfunction "PH14_E13") (pintype "passive"))
    )
    (net (code "306") (name "Net-(U3B-PH15)") (class "Default")
      (node (ref "R290") (pin "2") (pinfunction "2_2") (pintype "passive"))
      (node (ref "U3") (pin "D13") (pinfunction "PH15_D13") (pintype "passive"))
    )
    (net (code "307") (name "Net-(U3B-PI0)") (class "Default")
      (node (ref "R277") (pin "2") (pinfunction "2_2") (pintype "passive"))
      (node (ref "U3") (pin "E14") (pinfunction "PI0_E14") (pintype "passive"))
    )
    (net (code "308") (name "Net-(U3B-PI1)") (class "Default")
      (node (ref "R276") (pin "2") (pinfunction "2_2") (pintype "passive"))
      (node (ref "U3") (pin "D14") (pinfunction "PI1_D14") (pintype "passive"))
    )
    (net (code "309") (name "Net-(U3B-PI2)") (class "Default")
      (node (ref "R275") (pin "2") (pinfunction "2_2") (pintype "passive"))
      (node (ref "U3") (pin "C14") (pinfunction "PI2_C14") (pintype "passive"))
    )
    (net (code "310") (name "Net-(U3B-PI3)") (class "Default")
      (node (ref "R289") (pin "2") (pinfunction "2_2") (pintype "passive"))
      (node (ref "U3") (pin "C13") (pinfunction "PI3_C13") (pintype "passive"))
    )
    (net (code "311") (name "Net-(U3B-PI6)") (class "Default")
      (node (ref "R247") (pin "2") (pinfunction "2_2") (pintype "passive"))
      (node (ref "U3") (pin "D6") (pinfunction "PI6_D6") (pintype "passive"))
    )
    (net (code "312") (name "Net-(U3B-PI7)") (class "Default")
      (node (ref "R237") (pin "2") (pinfunction "2_2") (pintype "passive"))
      (node (ref "U3") (pin "D4") (pinfunction "PI7_D4") (pintype "passive"))
    )
    (net (code "313") (name "Net-(U3B-PI9)") (class "Default")
      (node (ref "R241") (pin "2") (pinfunction "2_2") (pintype "passive"))
      (node (ref "U3") (pin "E4") (pinfunction "PI9_E4") (pintype "passive"))
    )
    (net (code "314") (name "Net-(U3B-PI10)") (class "Default")
      (node (ref "R244") (pin "2") (pinfunction "2_2") (pintype "passive"))
      (node (ref "R43") (pin "2") (pinfunction "2_2") (pintype "passive"))
      (node (ref "U3") (pin "D5") (pinfunction "PI10_D5") (pintype "passive"))
    )
    (net (code "315") (name "Net-(U3B-PI14)") (class "Default")
      (node (ref "R295") (pin "2") (pinfunction "2_2") (pintype "passive"))
      (node (ref "U3") (pin "H3") (pinfunction "PI14_H3") (pintype "passive"))
    )
    (net (code "316") (name "Net-(U3C-BYPASS-REG)") (class "Default")
      (node (ref "R245") (pin "2") (pinfunction "2_2") (pintype "passive"))
      (node (ref "U3") (pin "L5") (pinfunction "BYPASS-REG_L5") (pintype "passive"))
    )
    (net (code "317") (name "Net-(U3C-VBAT)") (class "Default")
      (node (ref "JP8") (pin "2") (pintype "passive"))
      (node (ref "U3") (pin "C1") (pinfunction "VBAT_C1") (pintype "passive"))
    )
    (net (code "318") (name "Net-(U3C-VCAP1)") (class "Default")
      (node (ref "C133") (pin "1") (pinfunction "1_1") (pintype "passive"))
      (node (ref "U3") (pin "L11") (pinfunction "VCAP1_L11") (pintype "passive"))
    )
    (net (code "319") (name "Net-(U3C-VCAP2)") (class "Default")
      (node (ref "C32") (pin "1") (pinfunction "1_1") (pintype "passive"))
      (node (ref "U3") (pin "E11") (pinfunction "VCAP2_E11") (pintype "passive"))
    )
    (net (code "320") (name "VBUS_FS1") (class "Default")
      (node (ref "R266") (pin "2") (pinfunction "2_2") (pintype "passive"))
    )
    (net (code "321") (name "VBUS_FS2") (class "Default")
      (node (ref "R264") (pin "1") (pinfunction "1_1") (pintype "passive"))
    )
    (net (code "322") (name "VDDA") (class "Default")
      (node (ref "C108") (pin "1") (pinfunction "1_1") (pintype "passive"))
      (node (ref "C110") (pin "2") (pinfunction "2_2") (pintype "passive"))
      (node (ref "L10") (pin "2") (pinfunction "2_2") (pintype "passive"))
      (node (ref "R31") (pin "1") (pinfunction "1_1") (pintype "passive"))
      (node (ref "TP5") (pin "1") (pinfunction "1_1") (pintype "passive"))
      (node (ref "U3") (pin "R1") (pinfunction "VDDA_R1") (pintype "passive"))
    )
    (net (code "323") (name "VDD_MCU") (class "Default")
      (node (ref "C104") (pin "1") (pinfunction "1_1") (pintype "passive"))
      (node (ref "C105") (pin "1") (pinfunction "1_1") (pintype "passive"))
      (node (ref "C106") (pin "1") (pinfunction "1_1") (pintype "passive"))
      (node (ref "C109") (pin "1") (pinfunction "1_1") (pintype "passive"))
      (node (ref "C111") (pin "1") (pinfunction "1_1") (pintype "passive"))
      (node (ref "C112") (pin "1") (pinfunction "1_1") (pintype "passive"))
      (node (ref "C113") (pin "1") (pinfunction "1_1") (pintype "passive"))
      (node (ref "C114") (pin "1") (pinfunction "1_1") (pintype "passive"))
      (node (ref "C115") (pin "1") (pinfunction "1_1") (pintype "passive"))
      (node (ref "C118") (pin "1") (pinfunction "1_1") (pintype "passive"))
      (node (ref "C119") (pin "1") (pinfunction "1_1") (pintype "passive"))
      (node (ref "C120") (pin "1") (pinfunction "1_1") (pintype "passive"))
      (node (ref "C121") (pin "1") (pinfunction "1_1") (pintype "passive"))
      (node (ref "C122") (pin "1") (pinfunction "1_1") (pintype "passive"))
      (node (ref "C123") (pin "1") (pinfunction "1_1") (pintype "passive"))
      (node (ref "C125") (pin "1") (pinfunction "1_1") (pintype "passive"))
      (node (ref "C126") (pin "1") (pinfunction "1_1") (pintype "passive"))
      (node (ref "C127") (pin "1") (pinfunction "1_1") (pintype "passive"))
      (node (ref "C128") (pin "1") (pinfunction "1_1") (pintype "passive"))
      (node (ref "C129") (pin "1") (pinfunction "1_1") (pintype "passive"))
      (node (ref "C130") (pin "1") (pinfunction "1_1") (pintype "passive"))
      (node (ref "L10") (pin "1") (pinfunction "1_1") (pintype "passive"))
      (node (ref "U3") (pin "E10") (pinfunction "VDD15_E10") (pintype "passive"))
      (node (ref "U3") (pin "E7") (pinfunction "VDD3_E7") (pintype "passive"))
      (node (ref "U3") (pin "E8") (pinfunction "VDD11_E8") (pintype "passive"))
      (node (ref "U3") (pin "E9") (pinfunction "VDD10_E9") (pintype "passive"))
      (node (ref "U3") (pin "F11") (pinfunction "VDD2_F11") (pintype "passive"))
      (node (ref "U3") (pin "F4") (pinfunction "VDD13_F4") (pintype "passive"))
      (node (ref "U3") (pin "F5") (pinfunction "VDD17_F5") (pintype "passive"))
      (node (ref "U3") (pin "G11") (pinfunction "VDD9_G11") (pintype "passive"))
      (node (ref "U3") (pin "G5") (pinfunction "VDD18_G5") (pintype "passive"))
      (node (ref "U3") (pin "H11") (pinfunction "VDD20_H11") (pintype "passive"))
      (node (ref "U3") (pin "H5") (pinfunction "VDD5_H5") (pintype "passive"))
      (node (ref "U3") (pin "J11") (pinfunction "VDD8_J11") (pintype "passive"))
      (node (ref "U3") (pin "J5") (pinfunction "VDD12_J5") (pintype "passive"))
      (node (ref "U3") (pin "K11") (pinfunction "VDD14_K11") (pintype "passive"))
      (node (ref "U3") (pin "K5") (pinfunction "VDD4_K5") (pintype "passive"))
      (node (ref "U3") (pin "L10") (pinfunction "VDD1_L10") (pintype "passive"))
      (node (ref "U3") (pin "L7") (pinfunction "VDD19_L7") (pintype "passive"))
      (node (ref "U3") (pin "L8") (pinfunction "VDD6_L8") (pintype "passive"))
      (node (ref "U3") (pin "L9") (pinfunction "VDD7_L9") (pintype "passive"))
    )
    (net (code "324") (name "VREF+") (class "Default")
      (node (ref "C103") (pin "1") (pinfunction "1_1") (pintype "passive"))
      (node (ref "C107") (pin "2") (pinfunction "2_2") (pintype "passive"))
      (node (ref "R31") (pin "2") (pinfunction "2_2") (pintype "passive"))
      (node (ref "TP2") (pin "1") (pinfunction "1_1") (pintype "passive"))
      (node (ref "U3") (pin "P1") (pinfunction "VREF+_P1") (pintype "passive"))
    )
    (net (code "325") (name "unconnected-(X1-Pad2)") (class "Default")
      (node (ref "X1") (pin "2") (pinfunction "2_2") (pintype "passive+no_connect"))
    )
    (net (code "326") (name "unconnected-(X1-Pad3)") (class "Default")
      (node (ref "X1") (pin "3") (pinfunction "3_3") (pintype "passive+no_connect"))
    )
  )
)
